# schematics_Lampda_2024-07-19.net
KiCad netlist of a schematic drawn in Altium Designer
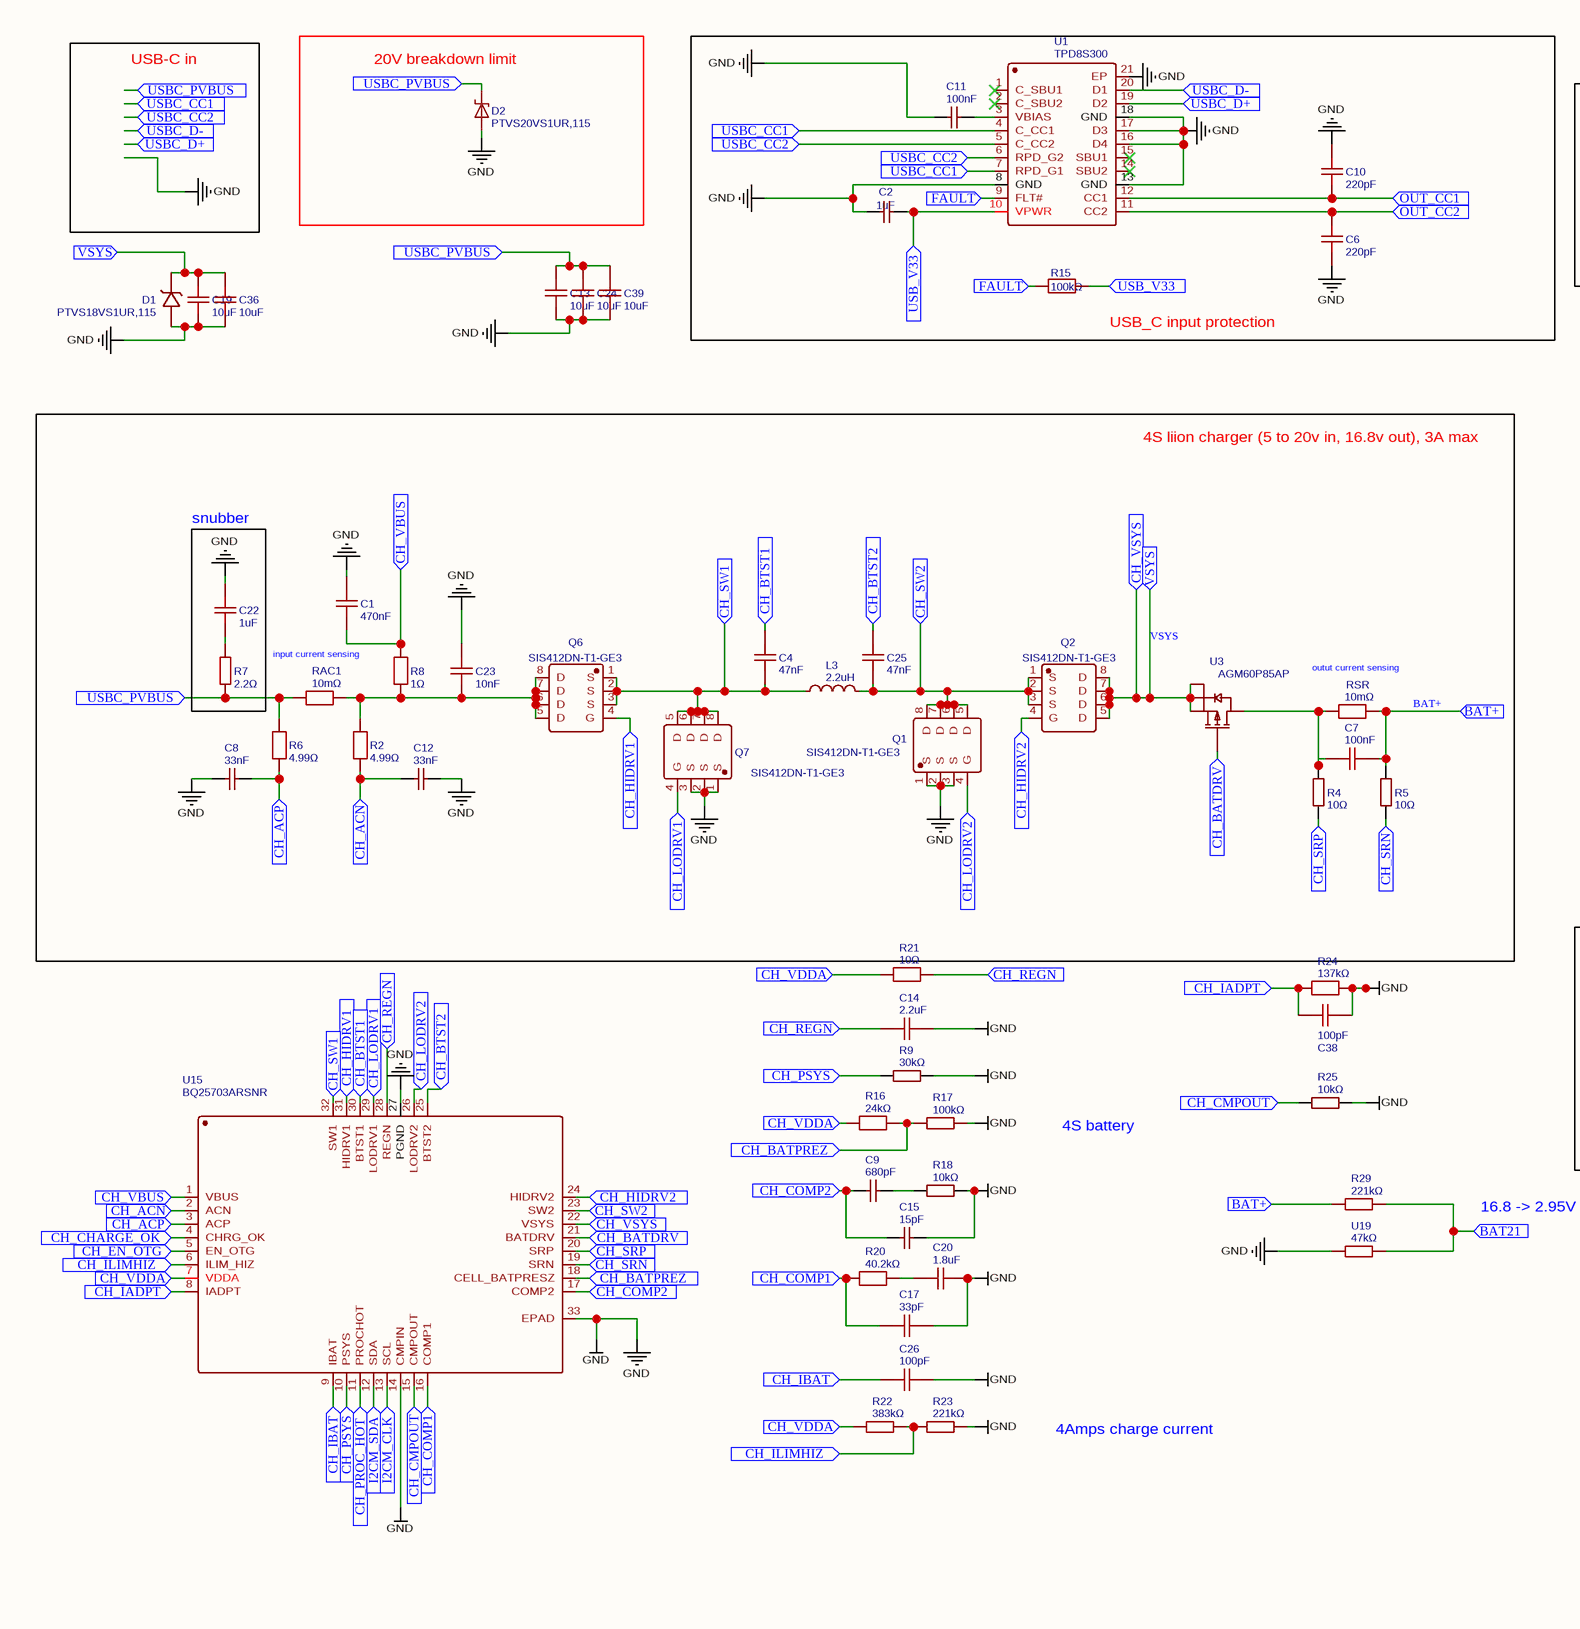
[diagram p0: schematics_Lampda_2024-07-19.schdoc, top left]
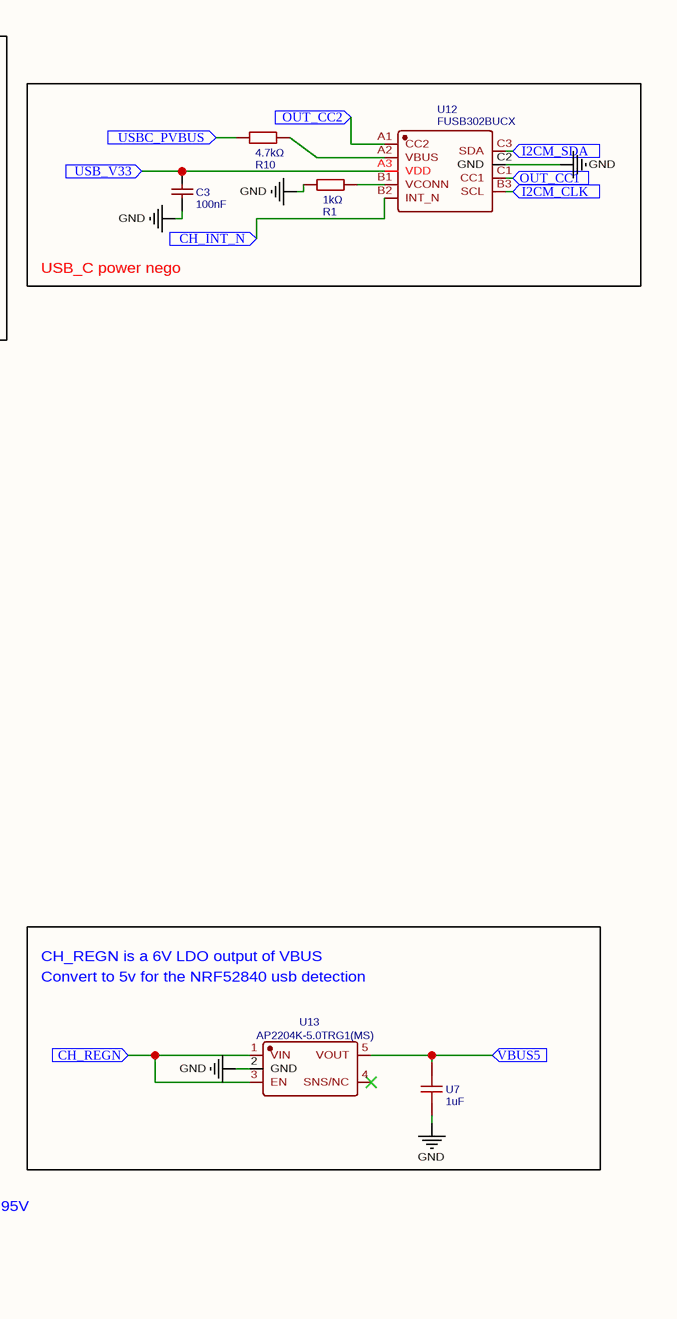
[diagram p1: schematics_Lampda_2024-07-19.schdoc, top right]
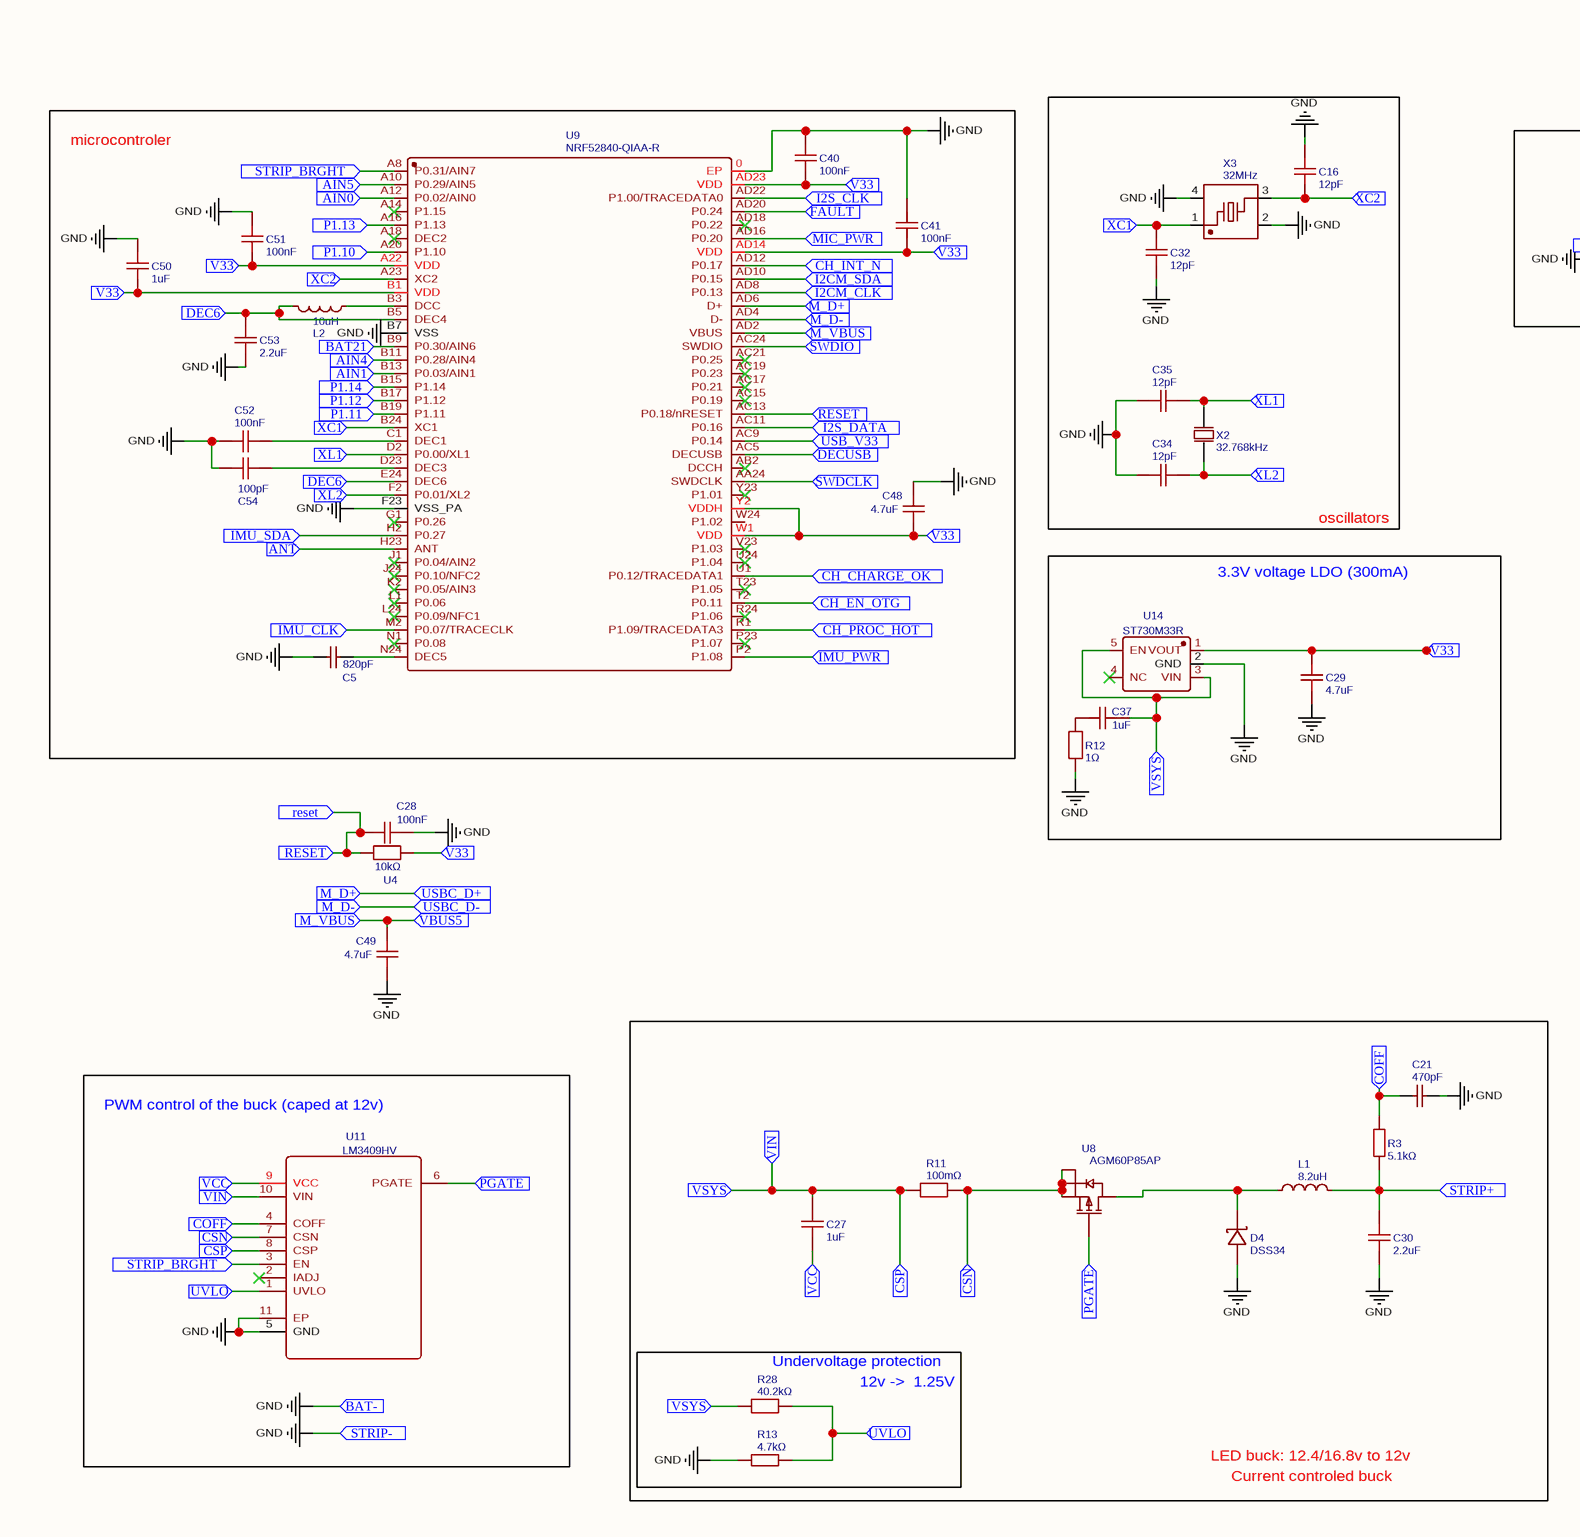
[diagram p2: schematics_Lampda_2024-07-19.schdoc, bottom left]
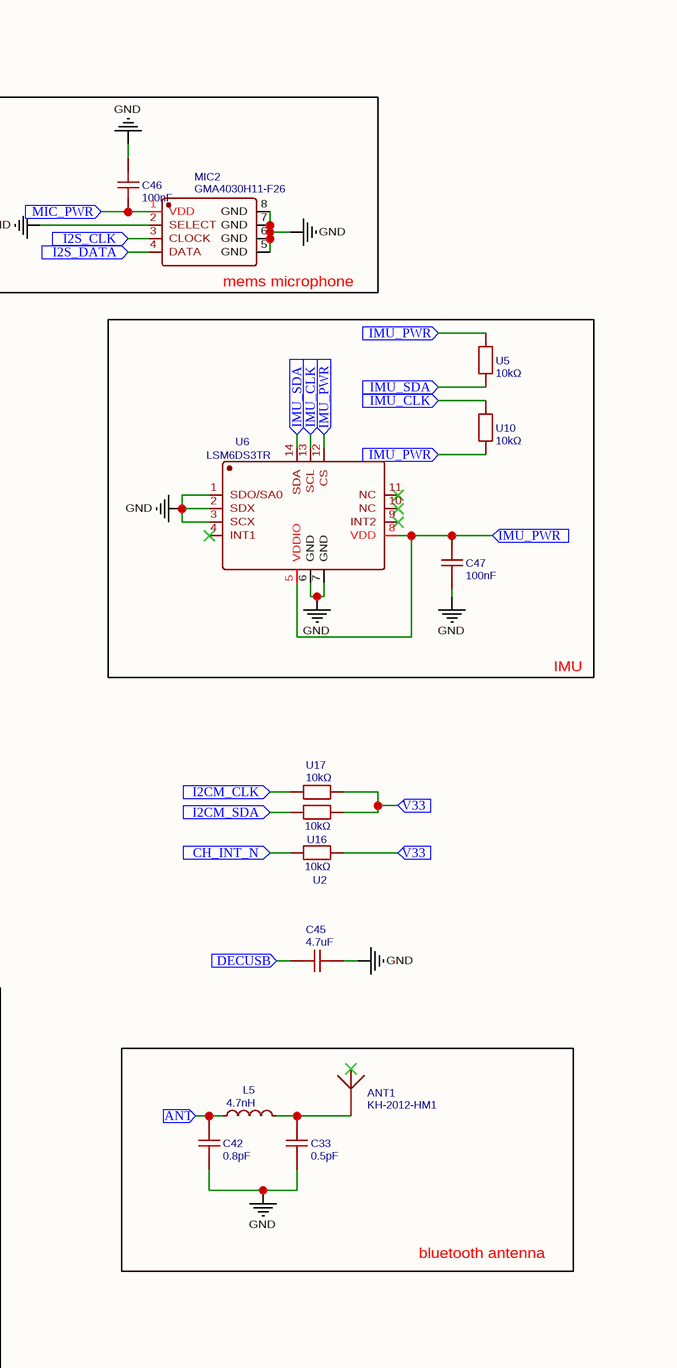
[diagram p3: schematics_Lampda_2024-07-19.schdoc, bottom right]

(export (version "E")
  (design (tool "Eeschema 10.0.6"))
  (components
    (comp (ref "ANT1")
      (value "KH-2012-HM1")
      (fields (field (name "MANUFACTURER") "kinghelm(金航标)") (field (name "CONTRIBUTOR") "lcsc"))
      (libsource (lib "altium-import") (part "root_0_KH-2012-HM1_"))
    )
    (comp (ref "C1")
      (value "470nF")
      (fields
        (field (name "MANUFACTURER") "YAGEO(国巨)")
        (field (name "MANUFACTURER PART") "CC0402KRX5R9BB474")
        (field (name "CONTRIBUTOR") "LCSC")
      )
      (libsource (lib "altium-import") (part "root_1_470nF_"))
    )
    (comp (ref "C2")
      (value "1uF")
      (fields
        (field (name "MANUFACTURER PART") "CL05A105KP5NNNC")
        (field (name "MANUFACTURER") "SAMSUNG(三星)")
      )
      (libsource (lib "altium-import") (part "root_0_1uF_"))
    )
    (comp (ref "C3")
      (value "100nF")
      (fields
        (field (name "MANUFACTURER") "YAGEO(国巨)")
        (field (name "MANUFACTURER PART") "CC0402KRX7R9BB104")
        (field (name "CONTRIBUTOR") "LCSC")
      )
      (libsource (lib "") (part "root_3_100nF__1"))
    )
    (comp (ref "C4")
      (value "47nF")
      (fields
        (field (name "MANUFACTURER") "CCTC(三环)")
        (field (name "MANUFACTURER PART") "TCC0402X7R473K500AT")
        (field (name "CONTRIBUTOR") "lcsc")
      )
      (libsource (lib "altium-import") (part "root_1_47nF_"))
    )
    (comp (ref "C5")
      (value "820pF")
      (fields (field (name "MANUFACTURER") "FH(风华)") (field (name "MANUFACTURER PART") "0402B821K500NT"))
      (libsource (lib "altium-import") (part "root_0_820pF_"))
    )
    (comp (ref "C6")
      (value "220pF")
      (fields
        (field (name "MANUFACTURER") "CCTC(三环)")
        (field (name "MANUFACTURER PART") "TCC0402X7R221K500AT")
        (field (name "CONTRIBUTOR") "LCSC")
      )
      (libsource (lib "altium-import") (part "root_0_220pF_"))
    )
    (comp (ref "C7")
      (value "100nF")
      (fields
        (field (name "MANUFACTURER") "Walsin(华新科)")
        (field (name "MANUFACTURER PART") "0402B104K250CT")
        (field (name "CONTRIBUTOR") "LCSC")
      )
      (libsource (lib "") (part "root_1_100nF__1"))
    )
    (comp (ref "C8")
      (value "33nF")
      (fields
        (field (name "MANUFACTURER") "YAGEO(国巨)")
        (field (name "MANUFACTURER PART") "CC0402KRX7R9BB333")
      )
      (libsource (lib "altium-import") (part "root_0_33nF_"))
    )
    (comp (ref "C9")
      (value "680pF")
      (fields (field (name "MANUFACTURER") "FH(风华)") (field (name "MANUFACTURER PART") "0402B681K500NT"))
      (libsource (lib "altium-import") (part "root_0_680pF_"))
    )
    (comp (ref "C10")
      (value "220pF")
      (fields
        (field (name "MANUFACTURER") "CCTC(三环)")
        (field (name "MANUFACTURER PART") "TCC0402X7R221K500AT")
        (field (name "CONTRIBUTOR") "LCSC")
      )
      (libsource (lib "altium-import") (part "root_0_220pF_"))
    )
    (comp (ref "C11")
      (value "100nF")
      (fields
        (field (name "MANUFACTURER") "YAGEO(国巨)")
        (field (name "MANUFACTURER PART") "CC0402KRX7R9BB104")
        (field (name "CONTRIBUTOR") "LCSC")
      )
      (libsource (lib "altium-import") (part "root_0_100nF_"))
    )
    (comp (ref "C12")
      (value "33nF")
      (fields
        (field (name "MANUFACTURER") "YAGEO(国巨)")
        (field (name "MANUFACTURER PART") "CC0402KRX7R9BB333")
      )
      (libsource (lib "altium-import") (part "root_0_33nF_"))
    )
    (comp (ref "C13")
      (value "10uF")
      (fields
        (field (name "MANUFACTURER") "muRata(村田)")
        (field (name "MANUFACTURER PART") "GRT21BC71E106KE13L")
        (field (name "CONTRIBUTOR") "lcsc")
      )
      (libsource (lib "altium-import") (part "root_1_10uF_"))
    )
    (comp (ref "C14")
      (value "2.2uF")
      (fields
        (field (name "MANUFACTURER") "FH(风华)")
        (field (name "MANUFACTURER PART") "0402X225K100NT")
        (field (name "CONTRIBUTOR") "LCSC")
      )
      (libsource (lib "altium-import") (part "root_0_2.2uF_"))
    )
    (comp (ref "C15")
      (value "15pF")
      (fields (field (name "MANUFACTURER") "FH(风华)") (field (name "MANUFACTURER PART") "0402CG150J500NT"))
      (libsource (lib "altium-import") (part "root_0_15pF_"))
    )
    (comp (ref "C16")
      (value "12pF")
      (fields
        (field (name "MANUFACTURER") "FH(风华)")
        (field (name "MANUFACTURER PART") "0402CG120F500NT")
        (field (name "CONTRIBUTOR") "LCSC")
      )
      (libsource (lib "altium-import") (part "root_1_12pF_"))
    )
    (comp (ref "C17")
      (value "33pF")
      (fields
        (field (name "MANUFACTURER") "Chinocera(华瓷)")
        (field (name "MANUFACTURER PART") "HGC0402G0330J500NTEJ")
        (field (name "CONTRIBUTOR") "LCSC")
      )
      (libsource (lib "altium-import") (part "root_0_33pF_"))
    )
    (comp (ref "C19")
      (value "10uF")
      (fields
        (field (name "MANUFACTURER") "muRata(村田)")
        (field (name "MANUFACTURER PART") "GRT21BC71E106KE13L")
        (field (name "CONTRIBUTOR") "lcsc")
      )
      (libsource (lib "altium-import") (part "root_1_10uF_"))
    )
    (comp (ref "C20")
      (value "1.8uF")
      (fields
        (field (name "MANUFACTURER") "CCTC(三环)")
        (field (name "MANUFACTURER PART") "TCC0603X5R185K160CT")
        (field (name "CONTRIBUTOR") "lcsc")
      )
      (libsource (lib "altium-import") (part "root_0_1.8uF_"))
    )
    (comp (ref "C21")
      (value "470pF")
      (fields
        (field (name "MANUFACTURER PART") "CL05B471KB5NNNC")
        (field (name "MANUFACTURER") "SAMSUNG(三星)")
      )
      (libsource (lib "altium-import") (part "root_0_470pF_"))
    )
    (comp (ref "C22")
      (value "1uF")
      (fields
        (field (name "MANUFACTURER") "SAMSUNG(三星)")
        (field (name "MANUFACTURER PART") "CL05A105KL5NRNC")
        (field (name "CONTRIBUTOR") "LCSC")
      )
      (libsource (lib "") (part "root_0_1uF__1"))
    )
    (comp (ref "C23")
      (value "10nF")
      (fields
        (field (name "MANUFACTURER") "YAGEO(国巨)")
        (field (name "MANUFACTURER PART") "CC0402JRX7R9BB103")
        (field (name "CONTRIBUTOR") "LCSC")
      )
      (libsource (lib "altium-import") (part "root_0_10nF_"))
    )
    (comp (ref "C24")
      (value "10uF")
      (fields
        (field (name "MANUFACTURER") "muRata(村田)")
        (field (name "MANUFACTURER PART") "GRT21BC71E106KE13L")
        (field (name "CONTRIBUTOR") "lcsc")
      )
      (libsource (lib "altium-import") (part "root_1_10uF_"))
    )
    (comp (ref "C25")
      (value "47nF")
      (fields
        (field (name "MANUFACTURER") "CCTC(三环)")
        (field (name "MANUFACTURER PART") "TCC0402X7R473K500AT")
        (field (name "CONTRIBUTOR") "lcsc")
      )
      (libsource (lib "altium-import") (part "root_1_47nF_"))
    )
    (comp (ref "C26")
      (value "100pF")
      (fields
        (field (name "MANUFACTURER") "YAGEO(国巨)")
        (field (name "MANUFACTURER PART") "CC0402JRX7R9BB101")
        (field (name "CONTRIBUTOR") "LCSC")
      )
      (libsource (lib "") (part "root_0_100pF__1"))
    )
    (comp (ref "C27")
      (value "1uF")
      (fields
        (field (name "MANUFACTURER") "SANYEAR(叁叶源)")
        (field (name "MANUFACTURER PART") "C0402X5R105K250NT")
        (field (name "CONTRIBUTOR") "LCSC")
      )
      (libsource (lib "") (part "root_1_1uF__2"))
    )
    (comp (ref "C28")
      (value "100nF")
      (fields (field (name "MANUFACTURER") "Walsin(华新科)") (field (name "MANUFACTURER PART") "0402B104K160CT"))
      (libsource (lib "") (part "root_0_100nF__1"))
    )
    (comp (ref "C29")
      (value "4.7uF")
      (fields
        (field (name "MANUFACTURER") "FH(风华)")
        (field (name "MANUFACTURER PART") "0402X475K100NT")
        (field (name "CONTRIBUTOR") "LCSC")
      )
      (libsource (lib "altium-import") (part "root_0_4.7uF_"))
    )
    (comp (ref "C30")
      (value "2.2uF")
      (fields
        (field (name "MANUFACTURER") "CCTC(三环)")
        (field (name "MANUFACTURER PART") "TCC0805X5R225K250FT")
        (field (name "CONTRIBUTOR") "lcsc")
      )
      (libsource (lib "altium-import") (part "root_1_2.2uF_"))
    )
    (comp (ref "C32")
      (value "12pF")
      (fields
        (field (name "MANUFACTURER") "FH(风华)")
        (field (name "MANUFACTURER PART") "0402CG120F500NT")
        (field (name "CONTRIBUTOR") "LCSC")
      )
      (libsource (lib "altium-import") (part "root_1_12pF_"))
    )
    (comp (ref "C33")
      (value "0.5pF")
      (fields
        (field (name "MANUFACTURER") "YAGEO(国巨)")
        (field (name "MANUFACTURER PART") "CC0402CRNPO9BNR50")
        (field (name "CONTRIBUTOR") "LCSC")
      )
      (libsource (lib "altium-import") (part "root_1_0.5pF_"))
    )
    (comp (ref "C34")
      (value "12pF")
      (fields
        (field (name "MANUFACTURER") "FH(风华)")
        (field (name "MANUFACTURER PART") "0402CG120F500NT")
        (field (name "CONTRIBUTOR") "LCSC")
      )
      (libsource (lib "altium-import") (part "root_2_12pF_"))
    )
    (comp (ref "C35")
      (value "12pF")
      (fields
        (field (name "MANUFACTURER") "FH(风华)")
        (field (name "MANUFACTURER PART") "0402CG120F500NT")
        (field (name "CONTRIBUTOR") "LCSC")
      )
      (libsource (lib "altium-import") (part "root_2_12pF_"))
    )
    (comp (ref "C36")
      (value "10uF")
      (fields
        (field (name "MANUFACTURER") "muRata(村田)")
        (field (name "MANUFACTURER PART") "GRT21BC71E106KE13L")
        (field (name "CONTRIBUTOR") "lcsc")
      )
      (libsource (lib "altium-import") (part "root_1_10uF_"))
    )
    (comp (ref "C37")
      (value "1uF")
      (fields
        (field (name "MANUFACTURER") "SAMSUNG(三星)")
        (field (name "MANUFACTURER PART") "CL05A105KL5NRNC")
        (field (name "CONTRIBUTOR") "LCSC")
      )
      (libsource (lib "altium-import") (part "root_1_1uF_"))
    )
    (comp (ref "C38")
      (value "100pF")
      (fields
        (field (name "MANUFACTURER") "YAGEO(国巨)")
        (field (name "MANUFACTURER PART") "CC0402JRX7R9BB101")
        (field (name "CONTRIBUTOR") "LCSC")
      )
      (libsource (lib "altium-import") (part "root_0_100pF_"))
    )
    (comp (ref "C39")
      (value "10uF")
      (fields
        (field (name "MANUFACTURER") "muRata(村田)")
        (field (name "MANUFACTURER PART") "GRT21BC71E106KE13L")
        (field (name "CONTRIBUTOR") "lcsc")
      )
      (libsource (lib "altium-import") (part "root_1_10uF_"))
    )
    (comp (ref "C40")
      (value "100nF")
      (fields (field (name "MANUFACTURER") "Walsin(华新科)") (field (name "MANUFACTURER PART") "0402B104K160CT"))
      (libsource (lib "altium-import") (part "root_1_100nF_"))
    )
    (comp (ref "C41")
      (value "100nF")
      (fields (field (name "MANUFACTURER") "Walsin(华新科)") (field (name "MANUFACTURER PART") "0402B104K160CT"))
      (libsource (lib "altium-import") (part "root_3_100nF_"))
    )
    (comp (ref "C42")
      (value "0.8pF")
      (fields
        (field (name "MANUFACTURER") "EYANG(宇阳科技)")
        (field (name "MANUFACTURER PART") "C0402C0G0R8C500NTB")
        (field (name "CONTRIBUTOR") "LCSC")
      )
      (libsource (lib "altium-import") (part "root_1_0.8pF_"))
    )
    (comp (ref "C45")
      (value "4.7uF")
      (fields
        (field (name "MANUFACTURER") "FH(风华)")
        (field (name "MANUFACTURER PART") "0402X475K100NT")
        (field (name "CONTRIBUTOR") "LCSC")
      )
      (libsource (lib "altium-import") (part "root_1_4.7uF_"))
    )
    (comp (ref "C46")
      (value "100nF")
      (fields
        (field (name "MANUFACTURER") "CCTC(三环)")
        (field (name "MANUFACTURER PART") "TCC0402X5R104K250AT")
        (field (name "CONTRIBUTOR") "lcsc")
      )
      (libsource (lib "altium-import") (part "root_1_100nF_"))
    )
    (comp (ref "C47")
      (value "100nF")
      (fields
        (field (name "MANUFACTURER") "CCTC(三环)")
        (field (name "MANUFACTURER PART") "TCC0402X5R104K250AT")
        (field (name "CONTRIBUTOR") "lcsc")
      )
      (libsource (lib "altium-import") (part "root_3_100nF_"))
    )
    (comp (ref "C48")
      (value "4.7uF")
      (fields
        (field (name "MANUFACTURER") "FH(风华)")
        (field (name "MANUFACTURER PART") "0402X475K100NT")
        (field (name "CONTRIBUTOR") "LCSC")
      )
      (libsource (lib "altium-import") (part "root_0_4.7uF_"))
    )
    (comp (ref "C49")
      (value "4.7uF")
      (fields
        (field (name "MANUFACTURER") "FH(风华)")
        (field (name "MANUFACTURER PART") "0402X475K100NT")
        (field (name "CONTRIBUTOR") "LCSC")
      )
      (libsource (lib "altium-import") (part "root_0_4.7uF_"))
    )
    (comp (ref "C50")
      (value "1uF")
      (fields
        (field (name "MANUFACTURER") "Walsin(华新科)")
        (field (name "MANUFACTURER PART") "0402X105K100CT")
        (field (name "CONTRIBUTOR") "LCSC")
      )
      (libsource (lib "") (part "root_1_1uF__1"))
    )
    (comp (ref "C51")
      (value "100nF")
      (fields (field (name "MANUFACTURER") "Walsin(华新科)") (field (name "MANUFACTURER PART") "0402B104K160CT"))
      (libsource (lib "altium-import") (part "root_1_100nF_"))
    )
    (comp (ref "C52")
      (value "100nF")
      (fields (field (name "MANUFACTURER") "Walsin(华新科)") (field (name "MANUFACTURER PART") "0402B104K160CT"))
      (libsource (lib "altium-import") (part "root_2_100nF_"))
    )
    (comp (ref "C53")
      (value "2.2uF")
      (fields
        (field (name "MANUFACTURER") "KEMET(基美)")
        (field (name "MANUFACTURER PART") "C0402C225M9PACTU")
        (field (name "CONTRIBUTOR") "LCSC")
      )
      (libsource (lib "altium-import") (part "root_1_2.2uF_"))
    )
    (comp (ref "C54")
      (value "100pF")
      (fields
        (field (name "MANUFACTURER") "CCTC(三环)")
        (field (name "MANUFACTURER PART") "TCC0402COG101K500AT")
        (field (name "CONTRIBUTOR") "LCSC")
      )
      (libsource (lib "altium-import") (part "root_0_100pF_"))
    )
    (comp (ref "D1")
      (value "PTVS18VS1UR,115")
      (fields (field (name "MANUFACTURER") "Nexperia(安世)") (field (name "CONTRIBUTOR") "LCSC"))
      (libsource (lib "altium-import") (part "root_3_PTVS18VS1UR,115_"))
    )
    (comp (ref "D2")
      (value "PTVS20VS1UR,115")
      (fields (field (name "MANUFACTURER") "Nexperia(安世)") (field (name "CONTRIBUTOR") "LCSC"))
      (libsource (lib "altium-import") (part "root_3_PTVS20VS1UR,115_"))
    )
    (comp (ref "D4")
      (value "DSS34")
      (fields (field (name "MANUFACTURER") "星海"))
      (libsource (lib "altium-import") (part "root_3_DSS34_"))
    )
    (comp (ref "L1")
      (value "8.2uH")
      (fields
        (field (name "MANUFACTURER") "cjiang(长江微电)")
        (field (name "MANUFACTURER PART") "FHD4020S-8R2MT")
        (field (name "CONTRIBUTOR") "LCSC")
      )
      (libsource (lib "altium-import") (part "root_0_8.2uH_"))
    )
    (comp (ref "L2")
      (value "10uH")
      (fields
        (field (name "MANUFACTURER") "Yanchuang(研创)")
        (field (name "MANUFACTURER PART") "SCMI201209X100KT")
        (field (name "CONTRIBUTOR") "LCSC")
      )
      (libsource (lib "altium-import") (part "root_0_10uH_"))
    )
    (comp (ref "L3")
      (value "2.2uH")
      (fields
        (field (name "MANUFACTURER") "SXN(顺翔诺)")
        (field (name "MANUFACTURER PART") "SMMS0420-2R2M")
        (field (name "CONTRIBUTOR") "LCSC")
      )
      (libsource (lib "altium-import") (part "root_0_2.2uH_"))
    )
    (comp (ref "L5")
      (value "4.7nH")
      (fields
        (field (name "MANUFACTURER") "chilisin(奇力新)")
        (field (name "MANUFACTURER PART") "CLH1005T-4N7S-S-NP")
      )
      (libsource (lib "altium-import") (part "root_0_4.7nH_"))
    )
    (comp (ref "MIC2")
      (value "GMA4030H11-F26")
      (fields (field (name "MANUFACTURER") "INGHAi(赢海)") (field (name "CONTRIBUTOR") "LCSC"))
      (libsource (lib "altium-import") (part "root_0_GMA4030H11-F26_"))
    )
    (comp (ref "Q1")
      (value "SIS412DN-T1-GE3")
      (fields (field (name "MANUFACTURER") "VISHAY(威世)"))
      (libsource (lib "") (part "root_3_SIS412DN-T1-GE3__1"))
    )
    (comp (ref "Q2")
      (value "SIS412DN-T1-GE3")
      (fields (field (name "MANUFACTURER") "VISHAY(威世)"))
      (libsource (lib "") (part "root_0_SIS412DN-T1-GE3__1"))
    )
    (comp (ref "Q6")
      (value "SIS412DN-T1-GE3")
      (fields (field (name "MANUFACTURER") "VISHAY(威世)"))
      (libsource (lib "altium-import") (part "root_0_SIS412DN-T1-GE3_"))
    )
    (comp (ref "Q7")
      (value "SIS412DN-T1-GE3")
      (fields (field (name "MANUFACTURER") "VISHAY(威世)"))
      (libsource (lib "altium-import") (part "root_3_SIS412DN-T1-GE3_"))
    )
    (comp (ref "R1")
      (value "1kΩ")
      (fields
        (field (name "MANUFACTURER") "EVER OHMS(天二科技)")
        (field (name "MANUFACTURER PART") "QR0402F1K00Q10Z")
        (field (name "CONTRIBUTOR") "LCSC")
      )
      (libsource (lib "altium-import") (part "root_2_1kΩ_"))
    )
    (comp (ref "R2")
      (value "4.99Ω")
      (fields
        (field (name "MANUFACTURER") "VISHAY(威世)")
        (field (name "MANUFACTURER PART") "CRCW04024R99FKED")
        (field (name "CONTRIBUTOR") "lcsc")
      )
      (libsource (lib "altium-import") (part "root_1_4.99Ω_"))
    )
    (comp (ref "R3")
      (value "5.1kΩ")
      (fields
        (field (name "MANUFACTURER") "Tyohm(幸亚电阻)")
        (field (name "MANUFACTURER PART") "RMC04025.1K5%N")
        (field (name "CONTRIBUTOR") "LCSC")
      )
      (libsource (lib "altium-import") (part "root_1_5.1kΩ_"))
    )
    (comp (ref "R4")
      (value "10Ω")
      (fields
        (field (name "MANUFACTURER") "UNI-ROYAL(厚声)")
        (field (name "MANUFACTURER PART") "0402WGF100JTCE")
      )
      (libsource (lib "altium-import") (part "root_1_10Ω_"))
    )
    (comp (ref "R5")
      (value "10Ω")
      (fields
        (field (name "MANUFACTURER") "UNI-ROYAL(厚声)")
        (field (name "MANUFACTURER PART") "0402WGF100JTCE")
      )
      (libsource (lib "altium-import") (part "root_1_10Ω_"))
    )
    (comp (ref "R6")
      (value "4.99Ω")
      (fields
        (field (name "MANUFACTURER") "VISHAY(威世)")
        (field (name "MANUFACTURER PART") "CRCW04024R99FKED")
        (field (name "CONTRIBUTOR") "lcsc")
      )
      (libsource (lib "altium-import") (part "root_1_4.99Ω_"))
    )
    (comp (ref "R7")
      (value "2.2Ω")
      (fields
        (field (name "MANUFACTURER") "Tyohm(幸亚电阻)")
        (field (name "MANUFACTURER PART") "RMC08052.25%N")
        (field (name "CONTRIBUTOR") "LCSC")
      )
      (libsource (lib "altium-import") (part "root_1_2.2Ω_"))
    )
    (comp (ref "R8")
      (value "1Ω")
      (fields
        (field (name "MANUFACTURER") "EVER OHMS(天二科技)")
        (field (name "MANUFACTURER PART") "CR0402F1R00Q10Z")
        (field (name "CONTRIBUTOR") "LCSC")
      )
      (libsource (lib "altium-import") (part "root_1_1Ω_"))
    )
    (comp (ref "R9")
      (value "30kΩ")
      (fields
        (field (name "MANUFACTURER") "UNI-ROYAL(厚声)")
        (field (name "MANUFACTURER PART") "0402WGF3002TCE")
      )
      (libsource (lib "altium-import") (part "root_0_30kΩ_"))
    )
    (comp (ref "R10")
      (value "4.7kΩ")
      (fields
        (field (name "MANUFACTURER") "Tyohm(幸亚电阻)")
        (field (name "MANUFACTURER PART") "RMC04024K7JN")
        (field (name "CONTRIBUTOR") "LCSC")
      )
      (libsource (lib "altium-import") (part "root_0_4.7kΩ_"))
    )
    (comp (ref "R11")
      (value "100mΩ")
      (fields
        (field (name "MANUFACTURER") "Milliohm(毫欧)")
        (field (name "MANUFACTURER PART") "HoRF1206-1/4W-100mR-1%")
        (field (name "CONTRIBUTOR") "lcsc")
      )
      (libsource (lib "altium-import") (part "root_0_100mΩ_"))
    )
    (comp (ref "R12")
      (value "1Ω")
      (fields
        (field (name "MANUFACTURER") "EVER OHMS(天二科技)")
        (field (name "MANUFACTURER PART") "CR0402F1R00Q10Z")
        (field (name "CONTRIBUTOR") "LCSC")
      )
      (libsource (lib "altium-import") (part "root_1_1Ω_"))
    )
    (comp (ref "R13")
      (value "4.7kΩ")
      (fields
        (field (name "MANUFACTURER") "Tyohm(幸亚电阻)")
        (field (name "MANUFACTURER PART") "RMC04024K7FN")
        (field (name "CONTRIBUTOR") "LCSC")
      )
      (libsource (lib "altium-import") (part "root_0_4.7kΩ_"))
    )
    (comp (ref "R15")
      (value "100kΩ")
      (fields
        (field (name "MANUFACTURER") "RALEC(旺诠)")
        (field (name "MANUFACTURER PART") "RAT021003FTH")
        (field (name "CONTRIBUTOR") "lcsc")
      )
      (libsource (lib "altium-import") (part "root_0_100kΩ_"))
    )
    (comp (ref "R16")
      (value "24kΩ")
      (fields
        (field (name "MANUFACTURER") "UNI-ROYAL(厚声)")
        (field (name "MANUFACTURER PART") "0402WGD2402TCE")
        (field (name "CONTRIBUTOR") "LCSC")
      )
      (libsource (lib "altium-import") (part "root_0_24kΩ_"))
    )
    (comp (ref "R17")
      (value "100kΩ")
      (fields
        (field (name "MANUFACTURER") "UNI-ROYAL(厚声)")
        (field (name "MANUFACTURER PART") "0402WGD1003TCE")
        (field (name "CONTRIBUTOR") "LCSC")
      )
      (libsource (lib "") (part "root_0_100kΩ__1"))
    )
    (comp (ref "R18")
      (value "10kΩ")
      (fields
        (field (name "MANUFACTURER") "UNI-ROYAL(厚声)")
        (field (name "MANUFACTURER PART") "0402WGF1002TCE")
      )
      (libsource (lib "altium-import") (part "root_0_10kΩ_"))
    )
    (comp (ref "R20")
      (value "40.2kΩ")
      (fields
        (field (name "MANUFACTURER") "EVER OHMS(天二科技)")
        (field (name "MANUFACTURER PART") "CR0402F40K2Q10Z")
        (field (name "CONTRIBUTOR") "LCSC")
      )
      (libsource (lib "altium-import") (part "root_0_40.2kΩ_"))
    )
    (comp (ref "R21")
      (value "10Ω")
      (fields
        (field (name "MANUFACTURER") "EVER OHMS(天二科技)")
        (field (name "MANUFACTURER PART") "CR0402F10R0Q10Z")
        (field (name "CONTRIBUTOR") "LCSC")
      )
      (libsource (lib "altium-import") (part "root_0_10Ω_"))
    )
    (comp (ref "R22")
      (value "383kΩ")
      (fields
        (field (name "MANUFACTURER") "Walsin(华新科)")
        (field (name "MANUFACTURER PART") "WR04X3833FTL")
        (field (name "CONTRIBUTOR") "LCSC")
      )
      (libsource (lib "altium-import") (part "root_0_383kΩ_"))
    )
    (comp (ref "R23")
      (value "221kΩ")
      (fields
        (field (name "MANUFACTURER") "YAGEO(国巨)")
        (field (name "MANUFACTURER PART") "RC0402FR-07221KL")
        (field (name "CONTRIBUTOR") "LCSC")
      )
      (libsource (lib "altium-import") (part "root_0_221kΩ_"))
    )
    (comp (ref "R24")
      (value "137kΩ")
      (fields
        (field (name "MANUFACTURER") "UNI-ROYAL(厚声)")
        (field (name "MANUFACTURER PART") "TC0250D1373TCE")
        (field (name "CONTRIBUTOR") "lcsc")
      )
      (libsource (lib "altium-import") (part "root_0_137kΩ_"))
    )
    (comp (ref "R25")
      (value "10kΩ")
      (fields
        (field (name "MANUFACTURER") "UNI-ROYAL(厚声)")
        (field (name "MANUFACTURER PART") "0402WGF1002TCE")
      )
      (libsource (lib "altium-import") (part "root_0_10kΩ_"))
    )
    (comp (ref "R28")
      (value "40.2kΩ")
      (fields
        (field (name "MANUFACTURER") "EVER OHMS(天二科技)")
        (field (name "MANUFACTURER PART") "CR0402F40K2Q10Z")
        (field (name "CONTRIBUTOR") "LCSC")
      )
      (libsource (lib "altium-import") (part "root_0_40.2kΩ_"))
    )
    (comp (ref "R29")
      (value "221kΩ")
      (fields
        (field (name "MANUFACTURER") "YAGEO(国巨)")
        (field (name "MANUFACTURER PART") "RC0402FR-07221KL")
        (field (name "CONTRIBUTOR") "LCSC")
      )
      (libsource (lib "altium-import") (part "root_0_221kΩ_"))
    )
    (comp (ref "RAC1")
      (value "10mΩ")
      (fields
        (field (name "MANUFACTURER") "Milliohm(毫欧)")
        (field (name "MANUFACTURER PART") "HoJLR1206-1W-10mR-1%")
        (field (name "CONTRIBUTOR") "LCSC")
      )
      (libsource (lib "altium-import") (part "root_0_10mΩ_"))
    )
    (comp (ref "RSR")
      (value "10mΩ")
      (fields
        (field (name "MANUFACTURER") "Milliohm(毫欧)")
        (field (name "MANUFACTURER PART") "HoJLR1206-1W-10mR-1%")
        (field (name "CONTRIBUTOR") "LCSC")
      )
      (libsource (lib "altium-import") (part "root_0_10mΩ_"))
    )
    (comp (ref "U1")
      (value "TPD8S300")
      (fields
        (field (name "MANUFACTURER") "TI(德州仪器)")
        (field (name "MANUFACTURER PART") "TPD8S300RUKR")
        (field (name "CONTRIBUTOR") "LCSC")
      )
      (libsource (lib "altium-import") (part "root_0_TPD8S300_"))
    )
    (comp (ref "U2")
      (value "10kΩ")
      (fields
        (field (name "MANUFACTURER") "RALEC(旺诠)")
        (field (name "MANUFACTURER PART") "RAT021002FTH")
        (field (name "CONTRIBUTOR") "lcsc")
      )
      (libsource (lib "altium-import") (part "root_2_10kΩ_"))
    )
    (comp (ref "U3")
      (value "AGM60P85AP")
      (fields (field (name "MANUFACTURER") "AGM-Semi(芯控源)") (field (name "CONTRIBUTOR") "lcsc"))
      (libsource (lib "altium-import") (part "root_3_AGM60P85AP_"))
    )
    (comp (ref "U4")
      (value "10kΩ")
      (fields
        (field (name "MANUFACTURER") "RALEC(旺诠)")
        (field (name "MANUFACTURER PART") "RAT021002FTH")
        (field (name "CONTRIBUTOR") "lcsc")
      )
      (libsource (lib "altium-import") (part "root_2_10kΩ_"))
    )
    (comp (ref "U5")
      (value "10kΩ")
      (fields
        (field (name "MANUFACTURER") "RALEC(旺诠)")
        (field (name "MANUFACTURER PART") "RAT021002FTH")
        (field (name "CONTRIBUTOR") "lcsc")
      )
      (libsource (lib "altium-import") (part "root_3_10kΩ_"))
    )
    (comp (ref "U6")
      (value "LSM6DS3TR")
      (fields (field (name "MANUFACTURER") "ST(意法半导体)") (field (name "CONTRIBUTOR") "LCSC"))
      (libsource (lib "altium-import") (part "root_0_LSM6DS3TR_"))
    )
    (comp (ref "U7")
      (value "1uF")
      (fields
        (field (name "MANUFACTURER") "Chinocera(华瓷)")
        (field (name "MANUFACTURER PART") "HGC0402R5105K250NTEJ")
        (field (name "CONTRIBUTOR") "lcsc")
      )
      (libsource (lib "") (part "root_1_1uF__2"))
    )
    (comp (ref "U8")
      (value "AGM60P85AP")
      (fields (field (name "MANUFACTURER") "AGM-Semi(芯控源)") (field (name "CONTRIBUTOR") "lcsc"))
      (libsource (lib "altium-import") (part "root_3_AGM60P85AP_"))
    )
    (comp (ref "U9")
      (value "NRF52840-QIAA-R")
      (fields (field (name "MANUFACTURER") "NORDIC") (field (name "CONTRIBUTOR") "LCSC"))
      (libsource (lib "altium-import") (part "root_0_NRF52840-QIAA-R_"))
    )
    (comp (ref "U10")
      (value "10kΩ")
      (fields
        (field (name "MANUFACTURER") "RALEC(旺诠)")
        (field (name "MANUFACTURER PART") "RAT021002FTH")
        (field (name "CONTRIBUTOR") "lcsc")
      )
      (libsource (lib "altium-import") (part "root_3_10kΩ_"))
    )
    (comp (ref "U11")
      (value "LM3409HV")
      (fields (field (name "MANUFACTURER") "TI(德州仪器)") (field (name "MANUFACTURER PART") "LM3409HVMY/NOPB"))
      (libsource (lib "altium-import") (part "root_0_LM3409HV_"))
    )
    (comp (ref "U12")
      (value "FUSB302BUCX")
      (fields (field (name "MANUFACTURER") "onsemi(安森美)") (field (name "CONTRIBUTOR") "LCSC"))
      (libsource (lib "altium-import") (part "root_0_FUSB302BUCX_"))
    )
    (comp (ref "U13")
      (value "AP2204K-5.0TRG1(MS)")
      (fields (field (name "MANUFACTURER") "MSKSEMI(美森科)") (field (name "CONTRIBUTOR") "lcsc"))
      (libsource (lib "altium-import") (part "root_0_AP2204K-5.0TRG1(MS)_"))
    )
    (comp (ref "U14")
      (value "ST730M33R")
      (fields (field (name "MANUFACTURER") "ST(意法半导体)") (field (name "CONTRIBUTOR") "lcsc"))
      (libsource (lib "altium-import") (part "root_0_ST730M33R_"))
    )
    (comp (ref "U15")
      (value "BQ25703ARSNR")
      (fields (field (name "MANUFACTURER") "TI(德州仪器)") (field (name "CONTRIBUTOR") "LCSC"))
      (libsource (lib "altium-import") (part "root_0_BQ25703ARSNR_"))
    )
    (comp (ref "U16")
      (value "10kΩ")
      (fields
        (field (name "MANUFACTURER") "RALEC(旺诠)")
        (field (name "MANUFACTURER PART") "RAT021002FTH")
        (field (name "CONTRIBUTOR") "lcsc")
      )
      (libsource (lib "altium-import") (part "root_2_10kΩ_"))
    )
    (comp (ref "U17")
      (value "10kΩ")
      (fields
        (field (name "MANUFACTURER") "RALEC(旺诠)")
        (field (name "MANUFACTURER PART") "RAT021002FTH")
        (field (name "CONTRIBUTOR") "lcsc")
      )
      (libsource (lib "") (part "root_2_10kΩ__1"))
    )
    (comp (ref "U19")
      (value "47kΩ")
      (fields
        (field (name "MANUFACTURER") "RESI(开步睿思）")
        (field (name "MANUFACTURER PART") "HPCR0402F47K0K9")
        (field (name "CONTRIBUTOR") "LCSC")
      )
      (libsource (lib "altium-import") (part "root_0_47kΩ_"))
    )
    (comp (ref "X2")
      (value "32.768kHz")
      (fields
        (field (name "MANUFACTURER") "ABRACON")
        (field (name "MANUFACTURER PART") "ABS06-32.768KHZ-6-1-T")
        (field (name "CONTRIBUTOR") "lcsc")
      )
      (libsource (lib "altium-import") (part "root_1_32.768kHz_"))
    )
    (comp (ref "X3")
      (value "32MHz")
      (fields
        (field (name "MANUFACTURER") "SCTF(星通时频)")
        (field (name "MANUFACTURER PART") "SX1B32.000F1210F30")
        (field (name "CONTRIBUTOR") "lcsc")
      )
      (libsource (lib "altium-import") (part "root_0_32MHz_"))
    )
  )
  (nets
    (net (code "1") (name "/AIN0") (class "Default")
      (node (ref "U9") (pin "A12") (pinfunction "P0.02/AIN0_A12") (pintype "passive"))
    )
    (net (code "2") (name "/AIN1") (class "Default")
      (node (ref "U9") (pin "B13") (pinfunction "P0.03/AIN1_B13") (pintype "passive"))
    )
    (net (code "3") (name "/AIN4") (class "Default")
      (node (ref "U9") (pin "B11") (pinfunction "P0.28/AIN4_B11") (pintype "passive"))
    )
    (net (code "4") (name "/AIN5") (class "Default")
      (node (ref "U9") (pin "A10") (pinfunction "P0.29/AIN5_A10") (pintype "passive"))
    )
    (net (code "5") (name "/ANT") (class "Default")
      (node (ref "C42") (pin "2") (pinfunction "2_2") (pintype "passive"))
      (node (ref "L5") (pin "1") (pinfunction "1_1") (pintype "passive"))
      (node (ref "U9") (pin "H23") (pinfunction "ANT_H23") (pintype "passive"))
    )
    (net (code "6") (name "/BAT+") (class "Default")
      (node (ref "C7") (pin "1") (pinfunction "1_1") (pintype "passive"))
      (node (ref "R29") (pin "1") (pinfunction "1_1") (pintype "passive"))
      (node (ref "R5") (pin "2") (pinfunction "2_2") (pintype "passive"))
      (node (ref "RSR") (pin "2") (pinfunction "2_2") (pintype "passive"))
    )
    (net (code "7") (name "/BAT21") (class "Default")
      (node (ref "R29") (pin "2") (pinfunction "2_2") (pintype "passive"))
      (node (ref "U19") (pin "2") (pinfunction "2_2") (pintype "passive"))
      (node (ref "U9") (pin "B9") (pinfunction "P0.30/AIN6_B9") (pintype "passive"))
    )
    (net (code "8") (name "/CH_ACN") (class "Default")
      (node (ref "C12") (pin "1") (pinfunction "1_1") (pintype "passive"))
      (node (ref "R2") (pin "1") (pinfunction "1_1") (pintype "passive"))
      (node (ref "U15") (pin "2") (pinfunction "ACN_2") (pintype "passive"))
    )
    (net (code "9") (name "/CH_ACP") (class "Default")
      (node (ref "C8") (pin "2") (pinfunction "2_2") (pintype "passive"))
      (node (ref "R6") (pin "1") (pinfunction "1_1") (pintype "passive"))
      (node (ref "U15") (pin "3") (pinfunction "ACP_3") (pintype "passive"))
    )
    (net (code "10") (name "/CH_BATDRV") (class "Default")
      (node (ref "U15") (pin "21") (pinfunction "BATDRV_21") (pintype "passive"))
      (node (ref "U3") (pin "4") (pinfunction "G_4") (pintype "passive"))
    )
    (net (code "11") (name "/CH_BATPREZ") (class "Default")
      (node (ref "R16") (pin "2") (pinfunction "2_2") (pintype "passive"))
      (node (ref "R17") (pin "1") (pinfunction "1_1") (pintype "passive"))
      (node (ref "U15") (pin "18") (pinfunction "CELL_BATPRESZ_18") (pintype "passive"))
    )
    (net (code "12") (name "/CH_BTST1") (class "Default")
      (node (ref "C4") (pin "2") (pinfunction "2_2") (pintype "passive"))
      (node (ref "U15") (pin "30") (pinfunction "BTST1_30") (pintype "passive"))
    )
    (net (code "13") (name "/CH_BTST2") (class "Default")
      (node (ref "C25") (pin "2") (pinfunction "2_2") (pintype "passive"))
      (node (ref "U15") (pin "25") (pinfunction "BTST2_25") (pintype "passive"))
    )
    (net (code "14") (name "/CH_CHARGE_OK") (class "Default")
      (node (ref "U15") (pin "4") (pinfunction "CHRG_OK_4") (pintype "passive"))
      (node (ref "U9") (pin "U1") (pinfunction "P0.12/TRACEDATA1_U1") (pintype "passive"))
    )
    (net (code "15") (name "/CH_CMPOUT") (class "Default")
      (node (ref "R25") (pin "1") (pinfunction "1_1") (pintype "passive"))
      (node (ref "U15") (pin "15") (pinfunction "CMPOUT_15") (pintype "passive"))
    )
    (net (code "16") (name "/CH_COMP1") (class "Default")
      (node (ref "C17") (pin "1") (pinfunction "1_1") (pintype "passive"))
      (node (ref "R20") (pin "1") (pinfunction "1_1") (pintype "passive"))
      (node (ref "U15") (pin "16") (pinfunction "COMP1_16") (pintype "passive"))
    )
    (net (code "17") (name "/CH_COMP2") (class "Default")
      (node (ref "C15") (pin "1") (pinfunction "1_1") (pintype "passive"))
      (node (ref "C9") (pin "1") (pinfunction "1_1") (pintype "passive"))
      (node (ref "U15") (pin "17") (pinfunction "COMP2_17") (pintype "passive"))
    )
    (net (code "18") (name "/CH_EN_OTG") (class "Default")
      (node (ref "U15") (pin "5") (pinfunction "EN_OTG_5") (pintype "passive"))
      (node (ref "U9") (pin "T2") (pinfunction "P0.11_T2") (pintype "passive"))
    )
    (net (code "19") (name "/CH_HIDRV1") (class "Default")
      (node (ref "Q6") (pin "4") (pinfunction "G_4") (pintype "passive"))
      (node (ref "U15") (pin "31") (pinfunction "HIDRV1_31") (pintype "passive"))
    )
    (net (code "20") (name "/CH_HIDRV2") (class "Default")
      (node (ref "Q2") (pin "4") (pinfunction "G_4") (pintype "passive"))
      (node (ref "U15") (pin "24") (pinfunction "HIDRV2_24") (pintype "passive"))
    )
    (net (code "21") (name "/CH_IADPT") (class "Default")
      (node (ref "C38") (pin "1") (pinfunction "1_1") (pintype "passive"))
      (node (ref "R24") (pin "1") (pinfunction "1_1") (pintype "passive"))
      (node (ref "U15") (pin "8") (pinfunction "IADPT_8") (pintype "passive"))
    )
    (net (code "22") (name "/CH_IBAT") (class "Default")
      (node (ref "C26") (pin "1") (pinfunction "1_1") (pintype "passive"))
      (node (ref "U15") (pin "9") (pinfunction "IBAT_9") (pintype "passive"))
    )
    (net (code "23") (name "/CH_ILIMHIZ") (class "Default")
      (node (ref "R22") (pin "2") (pinfunction "2_2") (pintype "passive"))
      (node (ref "R23") (pin "1") (pinfunction "1_1") (pintype "passive"))
      (node (ref "U15") (pin "6") (pinfunction "ILIM_HIZ_6") (pintype "passive"))
    )
    (net (code "24") (name "/CH_INT_N") (class "Default")
      (node (ref "U12") (pin "B2") (pinfunction "INT_N_B2") (pintype "passive"))
      (node (ref "U2") (pin "1") (pinfunction "1_1") (pintype "passive"))
      (node (ref "U9") (pin "AD12") (pinfunction "P0.17_AD12") (pintype "passive"))
    )
    (net (code "25") (name "/CH_LODRV1") (class "Default")
      (node (ref "Q7") (pin "4") (pinfunction "G_4") (pintype "passive"))
      (node (ref "U15") (pin "29") (pinfunction "LODRV1_29") (pintype "passive"))
    )
    (net (code "26") (name "/CH_LODRV2") (class "Default")
      (node (ref "Q1") (pin "4") (pinfunction "G_4") (pintype "passive"))
      (node (ref "U15") (pin "26") (pinfunction "LODRV2_26") (pintype "passive"))
    )
    (net (code "27") (name "/CH_PROC_HOT") (class "Default")
      (node (ref "U15") (pin "11") (pinfunction "PROCHOT_11") (pintype "passive"))
      (node (ref "U9") (pin "R1") (pinfunction "P1.09/TRACEDATA3_R1") (pintype "passive"))
    )
    (net (code "28") (name "/CH_PSYS") (class "Default")
      (node (ref "R9") (pin "1") (pinfunction "1_1") (pintype "passive"))
      (node (ref "U15") (pin "10") (pinfunction "PSYS_10") (pintype "passive"))
    )
    (net (code "29") (name "/CH_REGN") (class "Default")
      (node (ref "C14") (pin "1") (pinfunction "1_1") (pintype "passive"))
      (node (ref "R21") (pin "2") (pinfunction "2_2") (pintype "passive"))
      (node (ref "U13") (pin "1") (pinfunction "VIN_1") (pintype "passive"))
      (node (ref "U13") (pin "3") (pinfunction "EN_3") (pintype "passive"))
      (node (ref "U15") (pin "28") (pinfunction "REGN_28") (pintype "passive"))
    )
    (net (code "30") (name "/CH_SRN") (class "Default")
      (node (ref "R5") (pin "1") (pinfunction "1_1") (pintype "passive"))
      (node (ref "U15") (pin "19") (pinfunction "SRN_19") (pintype "passive"))
    )
    (net (code "31") (name "/CH_SRP") (class "Default")
      (node (ref "R4") (pin "1") (pinfunction "1_1") (pintype "passive"))
      (node (ref "U15") (pin "20") (pinfunction "SRP_20") (pintype "passive"))
    )
    (net (code "32") (name "/CH_SW1") (class "Default")
      (node (ref "C4") (pin "1") (pinfunction "1_1") (pintype "passive"))
      (node (ref "L3") (pin "1") (pinfunction "1_1") (pintype "passive"))
      (node (ref "Q6") (pin "1") (pinfunction "S_1") (pintype "passive"))
      (node (ref "Q6") (pin "2") (pinfunction "S_2") (pintype "passive"))
      (node (ref "Q6") (pin "3") (pinfunction "S_3") (pintype "passive"))
      (node (ref "Q7") (pin "5") (pinfunction "D_5") (pintype "passive"))
      (node (ref "Q7") (pin "6") (pinfunction "D_6") (pintype "passive"))
      (node (ref "Q7") (pin "7") (pinfunction "D_7") (pintype "passive"))
      (node (ref "Q7") (pin "8") (pinfunction "D_8") (pintype "passive"))
      (node (ref "U15") (pin "32") (pinfunction "SW1_32") (pintype "passive"))
    )
    (net (code "33") (name "/CH_SW2") (class "Default")
      (node (ref "C25") (pin "1") (pinfunction "1_1") (pintype "passive"))
      (node (ref "L3") (pin "2") (pinfunction "2_2") (pintype "passive"))
      (node (ref "Q1") (pin "5") (pinfunction "D_5") (pintype "passive"))
      (node (ref "Q1") (pin "6") (pinfunction "D_6") (pintype "passive"))
      (node (ref "Q1") (pin "7") (pinfunction "D_7") (pintype "passive"))
      (node (ref "Q1") (pin "8") (pinfunction "D_8") (pintype "passive"))
      (node (ref "Q2") (pin "1") (pinfunction "S_1") (pintype "passive"))
      (node (ref "Q2") (pin "2") (pinfunction "S_2") (pintype "passive"))
      (node (ref "Q2") (pin "3") (pinfunction "S_3") (pintype "passive"))
      (node (ref "U15") (pin "23") (pinfunction "SW2_23") (pintype "passive"))
    )
    (net (code "34") (name "/CH_VBUS") (class "Default")
      (node (ref "C1") (pin "1") (pinfunction "1_1") (pintype "passive"))
      (node (ref "R8") (pin "2") (pinfunction "2_2") (pintype "passive"))
      (node (ref "U15") (pin "1") (pinfunction "VBUS_1") (pintype "passive"))
    )
    (net (code "35") (name "/CH_VDDA") (class "Default")
      (node (ref "R16") (pin "1") (pinfunction "1_1") (pintype "passive"))
      (node (ref "R21") (pin "1") (pinfunction "1_1") (pintype "passive"))
      (node (ref "R22") (pin "1") (pinfunction "1_1") (pintype "passive"))
      (node (ref "U15") (pin "7") (pinfunction "VDDA_7") (pintype "passive"))
    )
    (net (code "36") (name "/COFF") (class "Default")
      (node (ref "C21") (pin "1") (pinfunction "1_1") (pintype "passive"))
      (node (ref "R3") (pin "2") (pinfunction "2_2") (pintype "passive"))
      (node (ref "U11") (pin "4") (pinfunction "COFF_4") (pintype "passive"))
    )
    (net (code "37") (name "/CSN") (class "Default")
      (node (ref "R11") (pin "2") (pinfunction "2_2") (pintype "passive"))
      (node (ref "U11") (pin "7") (pinfunction "CSN_7") (pintype "passive"))
      (node (ref "U8") (pin "1") (pinfunction "S_1") (pintype "passive"))
      (node (ref "U8") (pin "2") (pinfunction "S_2") (pintype "passive"))
      (node (ref "U8") (pin "3") (pinfunction "S_3") (pintype "passive"))
    )
    (net (code "38") (name "/DEC6") (class "Default")
      (node (ref "C53") (pin "2") (pinfunction "2_2") (pintype "passive"))
      (node (ref "L2") (pin "1") (pinfunction "1_1") (pintype "passive"))
      (node (ref "U9") (pin "B5") (pinfunction "DEC4_B5") (pintype "passive"))
      (node (ref "U9") (pin "E24") (pinfunction "DEC6_E24") (pintype "passive"))
    )
    (net (code "39") (name "/DECUSB") (class "Default")
      (node (ref "C45") (pin "2") (pinfunction "2_2") (pintype "passive"))
      (node (ref "U9") (pin "AC5") (pinfunction "DECUSB_AC5") (pintype "passive"))
    )
    (net (code "40") (name "/FAULT") (class "Default")
      (node (ref "R15") (pin "1") (pinfunction "1_1") (pintype "passive"))
      (node (ref "U1") (pin "9") (pinfunction "FLT#_9") (pintype "passive"))
      (node (ref "U9") (pin "AD20") (pinfunction "P0.24_AD20") (pintype "passive"))
    )
    (net (code "41") (name "/I2CM_CLK") (class "Default")
      (node (ref "U12") (pin "B3") (pinfunction "SCL_B3") (pintype "passive"))
      (node (ref "U15") (pin "13") (pinfunction "SCL_13") (pintype "passive"))
      (node (ref "U17") (pin "2") (pinfunction "2_2") (pintype "passive"))
      (node (ref "U9") (pin "AD8") (pinfunction "P0.13_AD8") (pintype "passive"))
    )
    (net (code "42") (name "/I2CM_SDA") (class "Default")
      (node (ref "U12") (pin "C3") (pinfunction "SDA_C3") (pintype "passive"))
      (node (ref "U15") (pin "12") (pinfunction "SDA_12") (pintype "passive"))
      (node (ref "U16") (pin "1") (pinfunction "1_1") (pintype "passive"))
      (node (ref "U9") (pin "AD10") (pinfunction "P0.15_AD10") (pintype "passive"))
    )
    (net (code "43") (name "/I2S_CLK") (class "Default")
      (node (ref "MIC2") (pin "3") (pinfunction "CLOCK_3") (pintype "passive"))
      (node (ref "U9") (pin "AD22") (pinfunction "P1.00/TRACEDATA0_AD22") (pintype "passive"))
    )
    (net (code "44") (name "/I2S_DATA") (class "Default")
      (node (ref "MIC2") (pin "4") (pinfunction "DATA_4") (pintype "passive"))
      (node (ref "U9") (pin "AC11") (pinfunction "P0.16_AC11") (pintype "passive"))
    )
    (net (code "45") (name "/IMU_CLK") (class "Default")
      (node (ref "U10") (pin "1") (pinfunction "1_1") (pintype "passive"))
      (node (ref "U6") (pin "13") (pinfunction "SCL_13") (pintype "passive"))
      (node (ref "U9") (pin "M2") (pinfunction "P0.07/TRACECLK_M2") (pintype "passive"))
    )
    (net (code "46") (name "/IMU_PWR") (class "Default")
      (node (ref "C47") (pin "1") (pinfunction "1_1") (pintype "passive"))
      (node (ref "U10") (pin "2") (pinfunction "2_2") (pintype "passive"))
      (node (ref "U5") (pin "1") (pinfunction "1_1") (pintype "passive"))
      (node (ref "U6") (pin "12") (pinfunction "CS_12") (pintype "passive"))
      (node (ref "U6") (pin "5") (pinfunction "VDDIO_5") (pintype "passive"))
      (node (ref "U6") (pin "8") (pinfunction "VDD_8") (pintype "passive"))
      (node (ref "U9") (pin "P2") (pinfunction "P1.08_P2") (pintype "passive"))
    )
    (net (code "47") (name "/IMU_SDA") (class "Default")
      (node (ref "U5") (pin "2") (pinfunction "2_2") (pintype "passive"))
      (node (ref "U6") (pin "14") (pinfunction "SDA_14") (pintype "passive"))
      (node (ref "U9") (pin "H2") (pinfunction "P0.27_H2") (pintype "passive"))
    )
    (net (code "48") (name "/MIC_PWR") (class "Default")
      (node (ref "C46") (pin "1") (pinfunction "1_1") (pintype "passive"))
      (node (ref "MIC2") (pin "1") (pinfunction "VDD_1") (pintype "passive"))
      (node (ref "U9") (pin "AD16") (pinfunction "P0.20_AD16") (pintype "passive"))
    )
    (net (code "49") (name "/M_D+") (class "Default")
      (node (ref "U1") (pin "19") (pinfunction "D2_19") (pintype "passive"))
      (node (ref "U9") (pin "AD6") (pinfunction "D+_AD6") (pintype "passive"))
    )
    (net (code "50") (name "/M_D-") (class "Default")
      (node (ref "U1") (pin "20") (pinfunction "D1_20") (pintype "passive"))
      (node (ref "U9") (pin "AD4") (pinfunction "D-_AD4") (pintype "passive"))
    )
    (net (code "51") (name "/M_VBUS") (class "Default")
      (node (ref "C49") (pin "2") (pinfunction "2_2") (pintype "passive"))
      (node (ref "U13") (pin "5") (pinfunction "VOUT_5") (pintype "passive"))
      (node (ref "U7") (pin "2") (pinfunction "2_2") (pintype "passive"))
      (node (ref "U9") (pin "AD2") (pinfunction "VBUS_AD2") (pintype "passive"))
    )
    (net (code "52") (name "/OUT_CC1") (class "Default")
      (node (ref "C10") (pin "2") (pinfunction "2_2") (pintype "passive"))
      (node (ref "U1") (pin "12") (pinfunction "CC1_12") (pintype "passive"))
      (node (ref "U12") (pin "C1") (pinfunction "CC1_C1") (pintype "passive"))
    )
    (net (code "53") (name "/OUT_CC2") (class "Default")
      (node (ref "C6") (pin "1") (pinfunction "1_1") (pintype "passive"))
      (node (ref "U1") (pin "11") (pinfunction "CC2_11") (pintype "passive"))
      (node (ref "U12") (pin "A1") (pinfunction "CC2_A1") (pintype "passive"))
    )
    (net (code "54") (name "/P1.10") (class "Default")
      (node (ref "U9") (pin "A20") (pinfunction "P1.10_A20") (pintype "passive"))
    )
    (net (code "55") (name "/P1.11") (class "Default")
      (node (ref "U9") (pin "B19") (pinfunction "P1.11_B19") (pintype "passive"))
    )
    (net (code "56") (name "/P1.12") (class "Default")
      (node (ref "U9") (pin "B17") (pinfunction "P1.12_B17") (pintype "passive"))
    )
    (net (code "57") (name "/P1.13") (class "Default")
      (node (ref "U9") (pin "A16") (pinfunction "P1.13_A16") (pintype "passive"))
    )
    (net (code "58") (name "/P1.14") (class "Default")
      (node (ref "U9") (pin "B15") (pinfunction "P1.14_B15") (pintype "passive"))
    )
    (net (code "59") (name "/PGATE") (class "Default")
      (node (ref "U11") (pin "6") (pinfunction "PGATE_6") (pintype "passive"))
      (node (ref "U8") (pin "4") (pinfunction "G_4") (pintype "passive"))
    )
    (net (code "60") (name "/RESET") (class "Default")
      (node (ref "C28") (pin "1") (pinfunction "1_1") (pintype "passive"))
      (node (ref "U4") (pin "1") (pinfunction "1_1") (pintype "passive"))
      (node (ref "U9") (pin "AC13") (pinfunction "P0.18/nRESET_AC13") (pintype "passive"))
    )
    (net (code "61") (name "/STRIP+") (class "Default")
      (node (ref "C30") (pin "2") (pinfunction "2_2") (pintype "passive"))
      (node (ref "L1") (pin "2") (pinfunction "2_2") (pintype "passive"))
      (node (ref "R3") (pin "1") (pinfunction "1_1") (pintype "passive"))
    )
    (net (code "62") (name "/STRIP_BRGHT") (class "Default")
      (node (ref "U11") (pin "3") (pinfunction "EN_3") (pintype "passive"))
      (node (ref "U9") (pin "A8") (pinfunction "P0.31/AIN7_A8") (pintype "passive"))
    )
    (net (code "63") (name "/SWDCLK") (class "Default")
      (node (ref "U9") (pin "AA24") (pinfunction "SWDCLK_AA24") (pintype "passive"))
    )
    (net (code "64") (name "/SWDIO") (class "Default")
      (node (ref "U9") (pin "AC24") (pinfunction "SWDIO_AC24") (pintype "passive"))
    )
    (net (code "65") (name "/USBC_CC1") (class "Default")
      (node (ref "U1") (pin "4") (pinfunction "C_CC1_4") (pintype "passive"))
      (node (ref "U1") (pin "7") (pinfunction "RPD_G1_7") (pintype "passive"))
    )
    (net (code "66") (name "/USBC_CC2") (class "Default")
      (node (ref "U1") (pin "5") (pinfunction "C_CC2_5") (pintype "passive"))
      (node (ref "U1") (pin "6") (pinfunction "RPD_G2_6") (pintype "passive"))
    )
    (net (code "67") (name "/USBC_PVBUS") (class "Default")
      (node (ref "C13") (pin "2") (pinfunction "2_2") (pintype "passive"))
      (node (ref "C24") (pin "2") (pinfunction "2_2") (pintype "passive"))
      (node (ref "C39") (pin "2") (pinfunction "2_2") (pintype "passive"))
      (node (ref "D2") (pin "1") (pinfunction "C_1") (pintype "passive"))
      (node (ref "R10") (pin "1") (pinfunction "1_1") (pintype "passive"))
      (node (ref "R6") (pin "2") (pinfunction "2_2") (pintype "passive"))
      (node (ref "R7") (pin "1") (pinfunction "1_1") (pintype "passive"))
      (node (ref "RAC1") (pin "1") (pinfunction "1_1") (pintype "passive"))
    )
    (net (code "68") (name "/USB_V33") (class "Default")
      (node (ref "C2") (pin "2") (pinfunction "2_2") (pintype "passive"))
      (node (ref "C3") (pin "1") (pinfunction "1_1") (pintype "passive"))
      (node (ref "R15") (pin "2") (pinfunction "2_2") (pintype "passive"))
      (node (ref "U1") (pin "10") (pinfunction "VPWR_10") (pintype "passive"))
      (node (ref "U12") (pin "A3") (pinfunction "VDD_A3") (pintype "passive"))
      (node (ref "U9") (pin "AC9") (pinfunction "P0.14_AC9") (pintype "passive"))
    )
    (net (code "69") (name "/UVLO") (class "Default")
      (node (ref "R13") (pin "2") (pinfunction "2_2") (pintype "passive"))
      (node (ref "R28") (pin "2") (pinfunction "2_2") (pintype "passive"))
      (node (ref "U11") (pin "1") (pinfunction "UVLO_1") (pintype "passive"))
    )
    (net (code "70") (name "/V33") (class "Default")
      (node (ref "C29") (pin "2") (pinfunction "2_2") (pintype "passive"))
      (node (ref "C40") (pin "1") (pinfunction "1_1") (pintype "passive"))
      (node (ref "C41") (pin "2") (pinfunction "2_2") (pintype "passive"))
      (node (ref "C48") (pin "1") (pinfunction "1_1") (pintype "passive"))
      (node (ref "C50") (pin "2") (pinfunction "2_2") (pintype "passive"))
      (node (ref "C51") (pin "1") (pinfunction "1_1") (pintype "passive"))
      (node (ref "U14") (pin "1") (pinfunction "VOUT_1") (pintype "passive"))
      (node (ref "U16") (pin "2") (pinfunction "2_2") (pintype "passive"))
      (node (ref "U17") (pin "1") (pinfunction "1_1") (pintype "passive"))
      (node (ref "U2") (pin "2") (pinfunction "2_2") (pintype "passive"))
      (node (ref "U4") (pin "2") (pinfunction "2_2") (pintype "passive"))
      (node (ref "U9") (pin "A22") (pinfunction "VDD_A22") (pintype "passive"))
      (node (ref "U9") (pin "AD14") (pinfunction "VDD_AD14") (pintype "passive"))
      (node (ref "U9") (pin "AD23") (pinfunction "VDD_AD23") (pintype "passive"))
      (node (ref "U9") (pin "B1") (pinfunction "VDD_B1") (pintype "passive"))
      (node (ref "U9") (pin "W1") (pinfunction "VDD_W1") (pintype "passive"))
      (node (ref "U9") (pin "Y2") (pinfunction "VDDH_Y2") (pintype "passive"))
    )
    (net (code "71") (name "/VCC") (class "Default")
      (node (ref "C27") (pin "1") (pinfunction "1_1") (pintype "passive"))
      (node (ref "U11") (pin "9") (pinfunction "VCC_9") (pintype "passive"))
    )
    (net (code "72") (name "/VSYS") (class "Default")
      (node (ref "C19") (pin "2") (pinfunction "2_2") (pintype "passive"))
      (node (ref "C27") (pin "2") (pinfunction "2_2") (pintype "passive"))
      (node (ref "C36") (pin "2") (pinfunction "2_2") (pintype "passive"))
      (node (ref "C37") (pin "2") (pinfunction "2_2") (pintype "passive"))
      (node (ref "D1") (pin "1") (pinfunction "1_1") (pintype "passive"))
      (node (ref "Q2") (pin "5") (pinfunction "D_5") (pintype "passive"))
      (node (ref "Q2") (pin "6") (pinfunction "D_6") (pintype "passive"))
      (node (ref "Q2") (pin "7") (pinfunction "D_7") (pintype "passive"))
      (node (ref "Q2") (pin "8") (pinfunction "D_8") (pintype "passive"))
      (node (ref "R11") (pin "1") (pinfunction "1_1") (pintype "passive"))
      (node (ref "R28") (pin "1") (pinfunction "1_1") (pintype "passive"))
      (node (ref "U11") (pin "10") (pinfunction "VIN_10") (pintype "passive"))
      (node (ref "U11") (pin "8") (pinfunction "CSP_8") (pintype "passive"))
      (node (ref "U14") (pin "3") (pinfunction "VIN_3") (pintype "passive"))
      (node (ref "U14") (pin "5") (pinfunction "EN_5") (pintype "passive"))
      (node (ref "U15") (pin "22") (pinfunction "VSYS_22") (pintype "passive"))
      (node (ref "U3") (pin "1") (pinfunction "S_1") (pintype "passive"))
      (node (ref "U3") (pin "2") (pinfunction "S_2") (pintype "passive"))
      (node (ref "U3") (pin "3") (pinfunction "S_3") (pintype "passive"))
    )
    (net (code "73") (name "/XC1") (class "Default")
      (node (ref "C32") (pin "1") (pinfunction "1_1") (pintype "passive"))
      (node (ref "U9") (pin "B24") (pinfunction "XC1_B24") (pintype "passive"))
      (node (ref "X3") (pin "1") (pinfunction "1_1") (pintype "passive"))
    )
    (net (code "74") (name "/XC2") (class "Default")
      (node (ref "C16") (pin "2") (pinfunction "2_2") (pintype "passive"))
      (node (ref "U9") (pin "A23") (pinfunction "XC2_A23") (pintype "passive"))
      (node (ref "X3") (pin "3") (pinfunction "3_3") (pintype "passive"))
    )
    (net (code "75") (name "/XL1") (class "Default")
      (node (ref "C35") (pin "2") (pinfunction "2_2") (pintype "passive"))
      (node (ref "U9") (pin "D2") (pinfunction "P0.00/XL1_D2") (pintype "passive"))
      (node (ref "X2") (pin "2") (pinfunction "OSC2_2") (pintype "passive"))
    )
    (net (code "76") (name "/XL2") (class "Default")
      (node (ref "C34") (pin "2") (pinfunction "2_2") (pintype "passive"))
      (node (ref "U9") (pin "F2") (pinfunction "P0.01/XL2_F2") (pintype "passive"))
      (node (ref "X2") (pin "1") (pinfunction "OSC1_1") (pintype "passive"))
    )
    (net (code "77") (name "GND") (class "Default")
      (node (ref "C1") (pin "2") (pinfunction "2_2") (pintype "passive"))
      (node (ref "C10") (pin "1") (pinfunction "1_1") (pintype "passive"))
      (node (ref "C11") (pin "1") (pinfunction "1_1") (pintype "passive"))
      (node (ref "C12") (pin "2") (pinfunction "2_2") (pintype "passive"))
      (node (ref "C13") (pin "1") (pinfunction "1_1") (pintype "passive"))
      (node (ref "C14") (pin "2") (pinfunction "2_2") (pintype "passive"))
      (node (ref "C15") (pin "2") (pinfunction "2_2") (pintype "passive"))
      (node (ref "C16") (pin "1") (pinfunction "1_1") (pintype "passive"))
      (node (ref "C17") (pin "2") (pinfunction "2_2") (pintype "passive"))
      (node (ref "C19") (pin "1") (pinfunction "1_1") (pintype "passive"))
      (node (ref "C2") (pin "1") (pinfunction "1_1") (pintype "passive"))
      (node (ref "C20") (pin "2") (pinfunction "2_2") (pintype "passive"))
      (node (ref "C21") (pin "2") (pinfunction "2_2") (pintype "passive"))
      (node (ref "C22") (pin "1") (pinfunction "1_1") (pintype "passive"))
      (node (ref "C23") (pin "2") (pinfunction "2_2") (pintype "passive"))
      (node (ref "C24") (pin "1") (pinfunction "1_1") (pintype "passive"))
      (node (ref "C26") (pin "2") (pinfunction "2_2") (pintype "passive"))
      (node (ref "C28") (pin "2") (pinfunction "2_2") (pintype "passive"))
      (node (ref "C29") (pin "1") (pinfunction "1_1") (pintype "passive"))
      (node (ref "C3") (pin "2") (pinfunction "2_2") (pintype "passive"))
      (node (ref "C30") (pin "1") (pinfunction "1_1") (pintype "passive"))
      (node (ref "C32") (pin "2") (pinfunction "2_2") (pintype "passive"))
      (node (ref "C33") (pin "2") (pinfunction "2_2") (pintype "passive"))
      (node (ref "C34") (pin "1") (pinfunction "1_1") (pintype "passive"))
      (node (ref "C35") (pin "1") (pinfunction "1_1") (pintype "passive"))
      (node (ref "C36") (pin "1") (pinfunction "1_1") (pintype "passive"))
      (node (ref "C38") (pin "2") (pinfunction "2_2") (pintype "passive"))
      (node (ref "C39") (pin "1") (pinfunction "1_1") (pintype "passive"))
      (node (ref "C40") (pin "2") (pinfunction "2_2") (pintype "passive"))
      (node (ref "C41") (pin "1") (pinfunction "1_1") (pintype "passive"))
      (node (ref "C42") (pin "1") (pinfunction "1_1") (pintype "passive"))
      (node (ref "C45") (pin "1") (pinfunction "1_1") (pintype "passive"))
      (node (ref "C46") (pin "2") (pinfunction "2_2") (pintype "passive"))
      (node (ref "C47") (pin "2") (pinfunction "2_2") (pintype "passive"))
      (node (ref "C48") (pin "2") (pinfunction "2_2") (pintype "passive"))
      (node (ref "C49") (pin "1") (pinfunction "1_1") (pintype "passive"))
      (node (ref "C5") (pin "1") (pinfunction "1_1") (pintype "passive"))
      (node (ref "C50") (pin "1") (pinfunction "1_1") (pintype "passive"))
      (node (ref "C51") (pin "2") (pinfunction "2_2") (pintype "passive"))
      (node (ref "C52") (pin "2") (pinfunction "2_2") (pintype "passive"))
      (node (ref "C53") (pin "1") (pinfunction "1_1") (pintype "passive"))
      (node (ref "C54") (pin "1") (pinfunction "1_1") (pintype "passive"))
      (node (ref "C6") (pin "2") (pinfunction "2_2") (pintype "passive"))
      (node (ref "C8") (pin "1") (pinfunction "1_1") (pintype "passive"))
      (node (ref "D1") (pin "2") (pinfunction "2_2") (pintype "passive"))
      (node (ref "D2") (pin "2") (pinfunction "A_2") (pintype "passive"))
      (node (ref "D4") (pin "2") (pinfunction "A_2") (pintype "passive"))
      (node (ref "MIC2") (pin "2") (pinfunction "SELECT_2") (pintype "passive"))
      (node (ref "MIC2") (pin "5") (pinfunction "GND_5") (pintype "passive"))
      (node (ref "MIC2") (pin "6") (pinfunction "GND_6") (pintype "passive"))
      (node (ref "MIC2") (pin "7") (pinfunction "GND_7") (pintype "passive"))
      (node (ref "MIC2") (pin "8") (pinfunction "GND_8") (pintype "passive"))
      (node (ref "Q1") (pin "1") (pinfunction "S_1") (pintype "passive"))
      (node (ref "Q1") (pin "2") (pinfunction "S_2") (pintype "passive"))
      (node (ref "Q1") (pin "3") (pinfunction "S_3") (pintype "passive"))
      (node (ref "Q7") (pin "1") (pinfunction "S_1") (pintype "passive"))
      (node (ref "Q7") (pin "2") (pinfunction "S_2") (pintype "passive"))
      (node (ref "Q7") (pin "3") (pinfunction "S_3") (pintype "passive"))
      (node (ref "R1") (pin "2") (pinfunction "2_2") (pintype "passive"))
      (node (ref "R12") (pin "1") (pinfunction "1_1") (pintype "passive"))
      (node (ref "R13") (pin "1") (pinfunction "1_1") (pintype "passive"))
      (node (ref "R17") (pin "2") (pinfunction "2_2") (pintype "passive"))
      (node (ref "R18") (pin "2") (pinfunction "2_2") (pintype "passive"))
      (node (ref "R23") (pin "2") (pinfunction "2_2") (pintype "passive"))
      (node (ref "R24") (pin "2") (pinfunction "2_2") (pintype "passive"))
      (node (ref "R25") (pin "2") (pinfunction "2_2") (pintype "passive"))
      (node (ref "R9") (pin "2") (pinfunction "2_2") (pintype "passive"))
      (node (ref "U1") (pin "13") (pinfunction "GND_13") (pintype "passive"))
      (node (ref "U1") (pin "16") (pinfunction "D4_16") (pintype "passive"))
      (node (ref "U1") (pin "17") (pinfunction "D3_17") (pintype "passive"))
      (node (ref "U1") (pin "18") (pinfunction "GND_18") (pintype "passive"))
      (node (ref "U1") (pin "21") (pinfunction "EP_21") (pintype "passive"))
      (node (ref "U1") (pin "8") (pinfunction "GND_8") (pintype "passive"))
      (node (ref "U11") (pin "11") (pinfunction "EP_11") (pintype "passive"))
      (node (ref "U11") (pin "5") (pinfunction "GND_5") (pintype "passive"))
      (node (ref "U12") (pin "C2") (pinfunction "GND_C2") (pintype "passive"))
      (node (ref "U13") (pin "2") (pinfunction "GND_2") (pintype "passive"))
      (node (ref "U14") (pin "2") (pinfunction "GND_2") (pintype "passive"))
      (node (ref "U15") (pin "14") (pinfunction "CMPIN_14") (pintype "passive"))
      (node (ref "U15") (pin "27") (pinfunction "PGND_27") (pintype "passive"))
      (node (ref "U15") (pin "33") (pinfunction "EPAD_33") (pintype "passive"))
      (node (ref "U19") (pin "1") (pinfunction "1_1") (pintype "passive"))
      (node (ref "U6") (pin "1") (pinfunction "SDO/SA0_1") (pintype "passive"))
      (node (ref "U6") (pin "2") (pinfunction "SDX_2") (pintype "passive"))
      (node (ref "U6") (pin "3") (pinfunction "SCX_3") (pintype "passive"))
      (node (ref "U6") (pin "6") (pinfunction "GND_6") (pintype "passive"))
      (node (ref "U6") (pin "7") (pinfunction "GND_7") (pintype "passive"))
      (node (ref "U7") (pin "1") (pinfunction "1_1") (pintype "passive"))
      (node (ref "U9") (pin "0") (pinfunction "EP_0") (pintype "passive"))
      (node (ref "U9") (pin "B7") (pinfunction "VSS_B7") (pintype "passive"))
      (node (ref "U9") (pin "F23") (pinfunction "VSS_PA_F23") (pintype "passive"))
      (node (ref "X3") (pin "2") (pinfunction "GND_2") (pintype "passive"))
      (node (ref "X3") (pin "4") (pinfunction "GND_4") (pintype "passive"))
    )
    (net (code "78") (name "Net-(ANT1-ANT)") (class "Default")
      (node (ref "ANT1") (pin "1") (pinfunction "ANT_1") (pintype "passive"))
      (node (ref "C33") (pin "1") (pinfunction "1_1") (pintype "passive"))
      (node (ref "L5") (pin "2") (pinfunction "2_2") (pintype "passive"))
    )
    (net (code "79") (name "Net-(C9-Pad2)") (class "Default")
      (node (ref "C9") (pin "2") (pinfunction "2_2") (pintype "passive"))
      (node (ref "R18") (pin "1") (pinfunction "1_1") (pintype "passive"))
    )
    (net (code "80") (name "Net-(C20-Pad1)") (class "Default")
      (node (ref "C20") (pin "1") (pinfunction "1_1") (pintype "passive"))
      (node (ref "R20") (pin "2") (pinfunction "2_2") (pintype "passive"))
    )
    (net (code "81") (name "Net-(C22-Pad2)") (class "Default")
      (node (ref "C22") (pin "2") (pinfunction "2_2") (pintype "passive"))
      (node (ref "R7") (pin "2") (pinfunction "2_2") (pintype "passive"))
    )
    (net (code "82") (name "Net-(C23-Pad1)") (class "Default")
      (node (ref "C23") (pin "1") (pinfunction "1_1") (pintype "passive"))
      (node (ref "Q6") (pin "5") (pinfunction "D_5") (pintype "passive"))
      (node (ref "Q6") (pin "6") (pinfunction "D_6") (pintype "passive"))
      (node (ref "Q6") (pin "7") (pinfunction "D_7") (pintype "passive"))
      (node (ref "Q6") (pin "8") (pinfunction "D_8") (pintype "passive"))
      (node (ref "R2") (pin "2") (pinfunction "2_2") (pintype "passive"))
      (node (ref "R8") (pin "1") (pinfunction "1_1") (pintype "passive"))
      (node (ref "RAC1") (pin "2") (pinfunction "2_2") (pintype "passive"))
    )
    (net (code "83") (name "Net-(C37-Pad1)") (class "Default")
      (node (ref "C37") (pin "1") (pinfunction "1_1") (pintype "passive"))
      (node (ref "R12") (pin "2") (pinfunction "2_2") (pintype "passive"))
    )
    (net (code "84") (name "Net-(D4-K)") (class "Default")
      (node (ref "D4") (pin "1") (pinfunction "K_1") (pintype "passive"))
      (node (ref "L1") (pin "1") (pinfunction "1_1") (pintype "passive"))
      (node (ref "U8") (pin "5") (pinfunction "D_5") (pintype "passive"))
    )
    (net (code "85") (name "Net-(U1-VBIAS)") (class "Default")
      (node (ref "C11") (pin "2") (pinfunction "2_2") (pintype "passive"))
      (node (ref "U1") (pin "3") (pinfunction "VBIAS_3") (pintype "passive"))
    )
    (net (code "86") (name "Net-(U3-D)") (class "Default")
      (node (ref "C7") (pin "2") (pinfunction "2_2") (pintype "passive"))
      (node (ref "R4") (pin "2") (pinfunction "2_2") (pintype "passive"))
      (node (ref "RSR") (pin "1") (pinfunction "1_1") (pintype "passive"))
      (node (ref "U3") (pin "5") (pinfunction "D_5") (pintype "passive"))
    )
    (net (code "87") (name "Net-(U9-DCC)") (class "Default")
      (node (ref "L2") (pin "2") (pinfunction "2_2") (pintype "passive"))
      (node (ref "U9") (pin "B3") (pinfunction "DCC_B3") (pintype "passive"))
    )
    (net (code "88") (name "Net-(U9-DEC1)") (class "Default")
      (node (ref "C52") (pin "1") (pinfunction "1_1") (pintype "passive"))
      (node (ref "U9") (pin "C1") (pinfunction "DEC1_C1") (pintype "passive"))
    )
    (net (code "89") (name "Net-(U9-DEC3)") (class "Default")
      (node (ref "C54") (pin "2") (pinfunction "2_2") (pintype "passive"))
      (node (ref "U9") (pin "D23") (pinfunction "DEC3_D23") (pintype "passive"))
    )
    (net (code "90") (name "Net-(U9-DEC5)") (class "Default")
      (node (ref "C5") (pin "2") (pinfunction "2_2") (pintype "passive"))
      (node (ref "U9") (pin "N24") (pinfunction "DEC5_N24") (pintype "passive"))
    )
    (net (code "91") (name "Net-(U12-VBUS)") (class "Default")
      (node (ref "R10") (pin "2") (pinfunction "2_2") (pintype "passive"))
      (node (ref "U12") (pin "A2") (pinfunction "VBUS_A2") (pintype "passive"))
    )
    (net (code "92") (name "Net-(U12-VCONN)") (class "Default")
      (node (ref "R1") (pin "1") (pinfunction "1_1") (pintype "passive"))
      (node (ref "U12") (pin "B1") (pinfunction "VCONN_B1") (pintype "passive"))
    )
    (net (code "93") (name "unconnected-(ANT1-Pad2)") (class "Default")
      (node (ref "ANT1") (pin "2") (pinfunction "2_2") (pintype "passive+no_connect"))
    )
    (net (code "94") (name "unconnected-(U1-C_SBU1-Pad1)") (class "Default")
      (node (ref "U1") (pin "1") (pinfunction "C_SBU1_1") (pintype "passive+no_connect"))
    )
    (net (code "95") (name "unconnected-(U1-C_SBU2-Pad2)") (class "Default")
      (node (ref "U1") (pin "2") (pinfunction "C_SBU2_2") (pintype "passive+no_connect"))
    )
    (net (code "96") (name "unconnected-(U1-SBU1-Pad15)") (class "Default")
      (node (ref "U1") (pin "15") (pinfunction "SBU1_15") (pintype "passive+no_connect"))
    )
    (net (code "97") (name "unconnected-(U1-SBU2-Pad14)") (class "Default")
      (node (ref "U1") (pin "14") (pinfunction "SBU2_14") (pintype "passive+no_connect"))
    )
    (net (code "98") (name "unconnected-(U6-INT1-Pad4)") (class "Default")
      (node (ref "U6") (pin "4") (pinfunction "INT1_4") (pintype "passive+no_connect"))
    )
    (net (code "99") (name "unconnected-(U6-INT2-Pad9)") (class "Default")
      (node (ref "U6") (pin "9") (pinfunction "INT2_9") (pintype "passive+no_connect"))
    )
    (net (code "100") (name "unconnected-(U6-NC-Pad10)") (class "Default")
      (node (ref "U6") (pin "10") (pinfunction "NC_10") (pintype "passive+no_connect"))
    )
    (net (code "101") (name "unconnected-(U6-NC-Pad11)") (class "Default")
      (node (ref "U6") (pin "11") (pinfunction "NC_11") (pintype "passive+no_connect"))
    )
    (net (code "102") (name "unconnected-(U9-DCCH-PadAB2)") (class "Default")
      (node (ref "U9") (pin "AB2") (pinfunction "DCCH_AB2") (pintype "passive+no_connect"))
    )
    (net (code "103") (name "unconnected-(U9-DEC2-PadA18)") (class "Default")
      (node (ref "U9") (pin "A18") (pinfunction "DEC2_A18") (pintype "passive+no_connect"))
    )
    (net (code "104") (name "unconnected-(U9-P0.04{slash}AIN2-PadJ1)") (class "Default")
      (node (ref "U9") (pin "J1") (pinfunction "P0.04/AIN2_J1") (pintype "passive+no_connect"))
    )
    (net (code "105") (name "unconnected-(U9-P0.05{slash}AIN3-PadK2)") (class "Default")
      (node (ref "U9") (pin "K2") (pinfunction "P0.05/AIN3_K2") (pintype "passive+no_connect"))
    )
    (net (code "106") (name "unconnected-(U9-P0.06-PadL1)") (class "Default")
      (node (ref "U9") (pin "L1") (pinfunction "P0.06_L1") (pintype "passive+no_connect"))
    )
    (net (code "107") (name "unconnected-(U9-P0.08-PadN1)") (class "Default")
      (node (ref "U9") (pin "N1") (pinfunction "P0.08_N1") (pintype "passive+no_connect"))
    )
    (net (code "108") (name "unconnected-(U9-P0.09{slash}NFC1-PadL24)") (class "Default")
      (node (ref "U9") (pin "L24") (pinfunction "P0.09/NFC1_L24") (pintype "passive+no_connect"))
    )
    (net (code "109") (name "unconnected-(U9-P0.10{slash}NFC2-PadJ24)") (class "Default")
      (node (ref "U9") (pin "J24") (pinfunction "P0.10/NFC2_J24") (pintype "passive+no_connect"))
    )
    (net (code "110") (name "unconnected-(U9-P0.19-PadAC15)") (class "Default")
      (node (ref "U9") (pin "AC15") (pinfunction "P0.19_AC15") (pintype "passive+no_connect"))
    )
    (net (code "111") (name "unconnected-(U9-P0.21-PadAC17)") (class "Default")
      (node (ref "U9") (pin "AC17") (pinfunction "P0.21_AC17") (pintype "passive+no_connect"))
    )
    (net (code "112") (name "unconnected-(U9-P0.22-PadAD18)") (class "Default")
      (node (ref "U9") (pin "AD18") (pinfunction "P0.22_AD18") (pintype "passive+no_connect"))
    )
    (net (code "113") (name "unconnected-(U9-P0.23-PadAC19)") (class "Default")
      (node (ref "U9") (pin "AC19") (pinfunction "P0.23_AC19") (pintype "passive+no_connect"))
    )
    (net (code "114") (name "unconnected-(U9-P0.25-PadAC21)") (class "Default")
      (node (ref "U9") (pin "AC21") (pinfunction "P0.25_AC21") (pintype "passive+no_connect"))
    )
    (net (code "115") (name "unconnected-(U9-P0.26-PadG1)") (class "Default")
      (node (ref "U9") (pin "G1") (pinfunction "P0.26_G1") (pintype "passive+no_connect"))
    )
    (net (code "116") (name "unconnected-(U9-P1.01-PadY23)") (class "Default")
      (node (ref "U9") (pin "Y23") (pinfunction "P1.01_Y23") (pintype "passive+no_connect"))
    )
    (net (code "117") (name "unconnected-(U9-P1.02-PadW24)") (class "Default")
      (node (ref "U9") (pin "W24") (pinfunction "P1.02_W24") (pintype "passive"))
    )
    (net (code "118") (name "unconnected-(U9-P1.03-PadV23)") (class "Default")
      (node (ref "U9") (pin "V23") (pinfunction "P1.03_V23") (pintype "passive+no_connect"))
    )
    (net (code "119") (name "unconnected-(U9-P1.04-PadU24)") (class "Default")
      (node (ref "U9") (pin "U24") (pinfunction "P1.04_U24") (pintype "passive+no_connect"))
    )
    (net (code "120") (name "unconnected-(U9-P1.05-PadT23)") (class "Default")
      (node (ref "U9") (pin "T23") (pinfunction "P1.05_T23") (pintype "passive+no_connect"))
    )
    (net (code "121") (name "unconnected-(U9-P1.06-PadR24)") (class "Default")
      (node (ref "U9") (pin "R24") (pinfunction "P1.06_R24") (pintype "passive+no_connect"))
    )
    (net (code "122") (name "unconnected-(U9-P1.07-PadP23)") (class "Default")
      (node (ref "U9") (pin "P23") (pinfunction "P1.07_P23") (pintype "passive+no_connect"))
    )
    (net (code "123") (name "unconnected-(U9-P1.15-PadA14)") (class "Default")
      (node (ref "U9") (pin "A14") (pinfunction "P1.15_A14") (pintype "passive+no_connect"))
    )
    (net (code "124") (name "unconnected-(U11-IADJ-Pad2)") (class "Default")
      (node (ref "U11") (pin "2") (pinfunction "IADJ_2") (pintype "passive+no_connect"))
    )
    (net (code "125") (name "unconnected-(U13-SNS{slash}NC-Pad4)") (class "Default")
      (node (ref "U13") (pin "4") (pinfunction "SNS/NC_4") (pintype "passive+no_connect"))
    )
    (net (code "126") (name "unconnected-(U14-NC-Pad4)") (class "Default")
      (node (ref "U14") (pin "4") (pinfunction "NC_4") (pintype "passive+no_connect"))
    )
  )
)
